# sensormain_Exodia_ver2.net
KiCad netlist of a schematic drawn in EAGLE
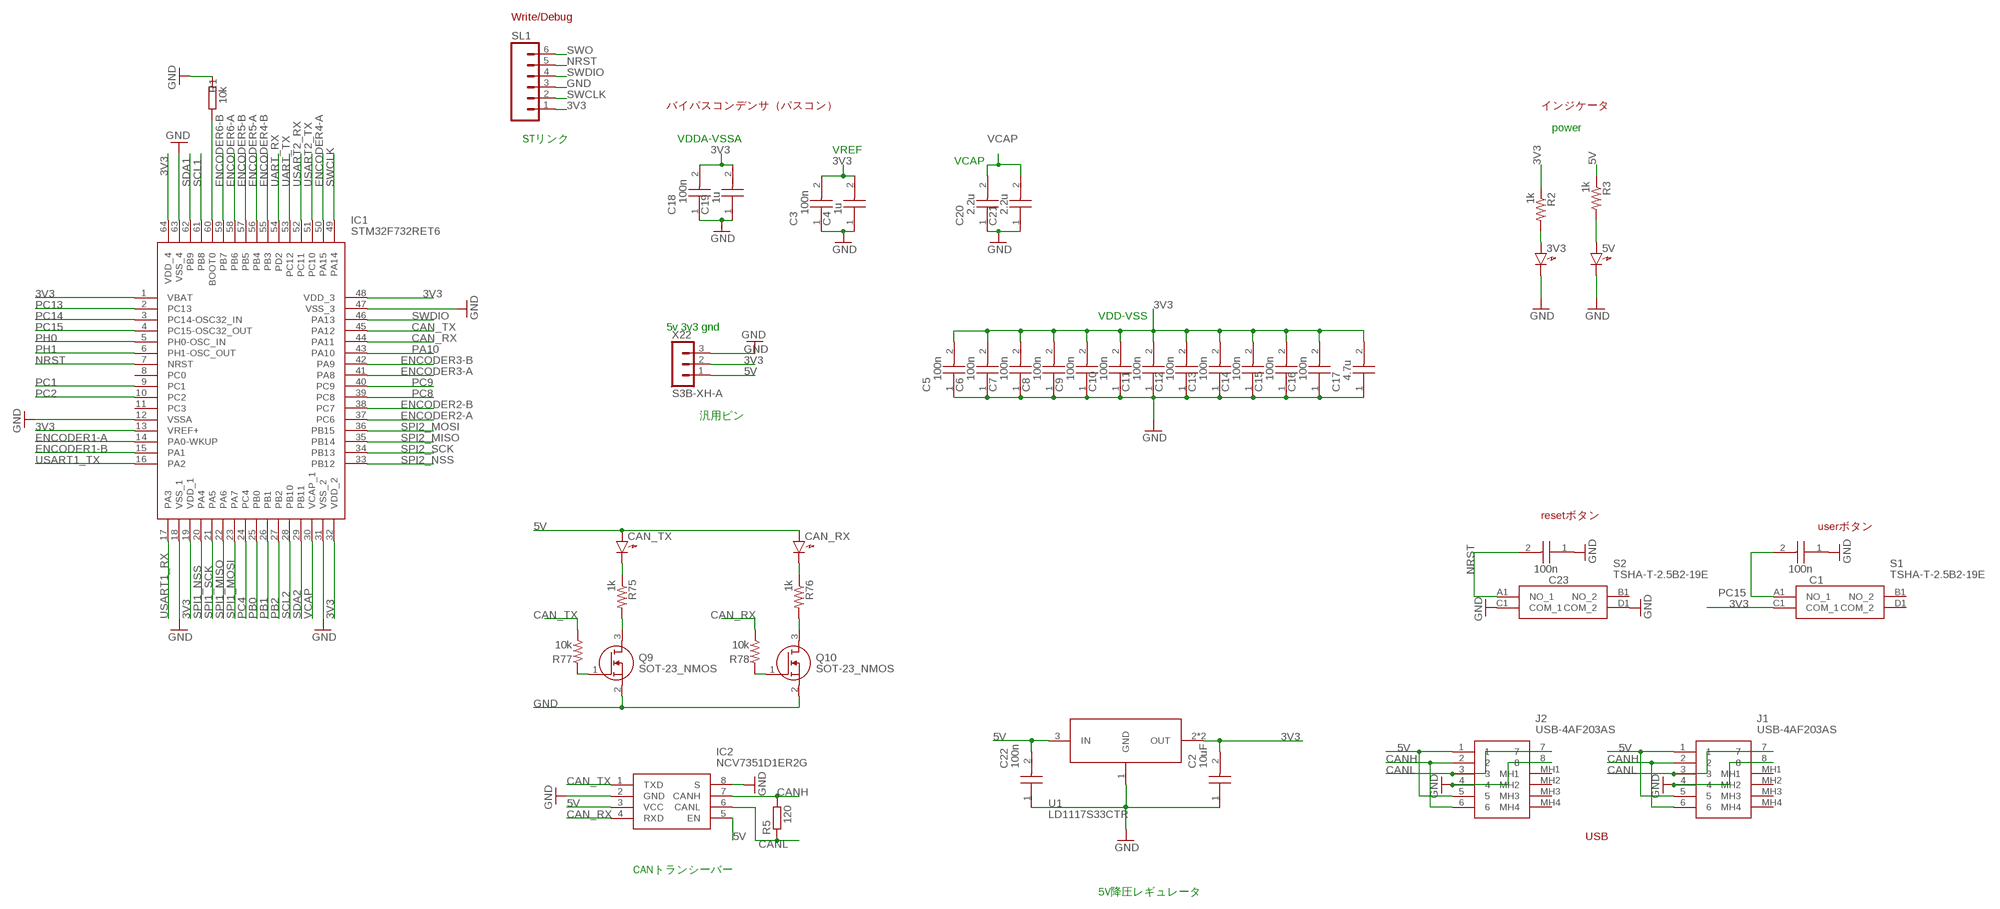
[diagram p0: schematic, sheet 1]
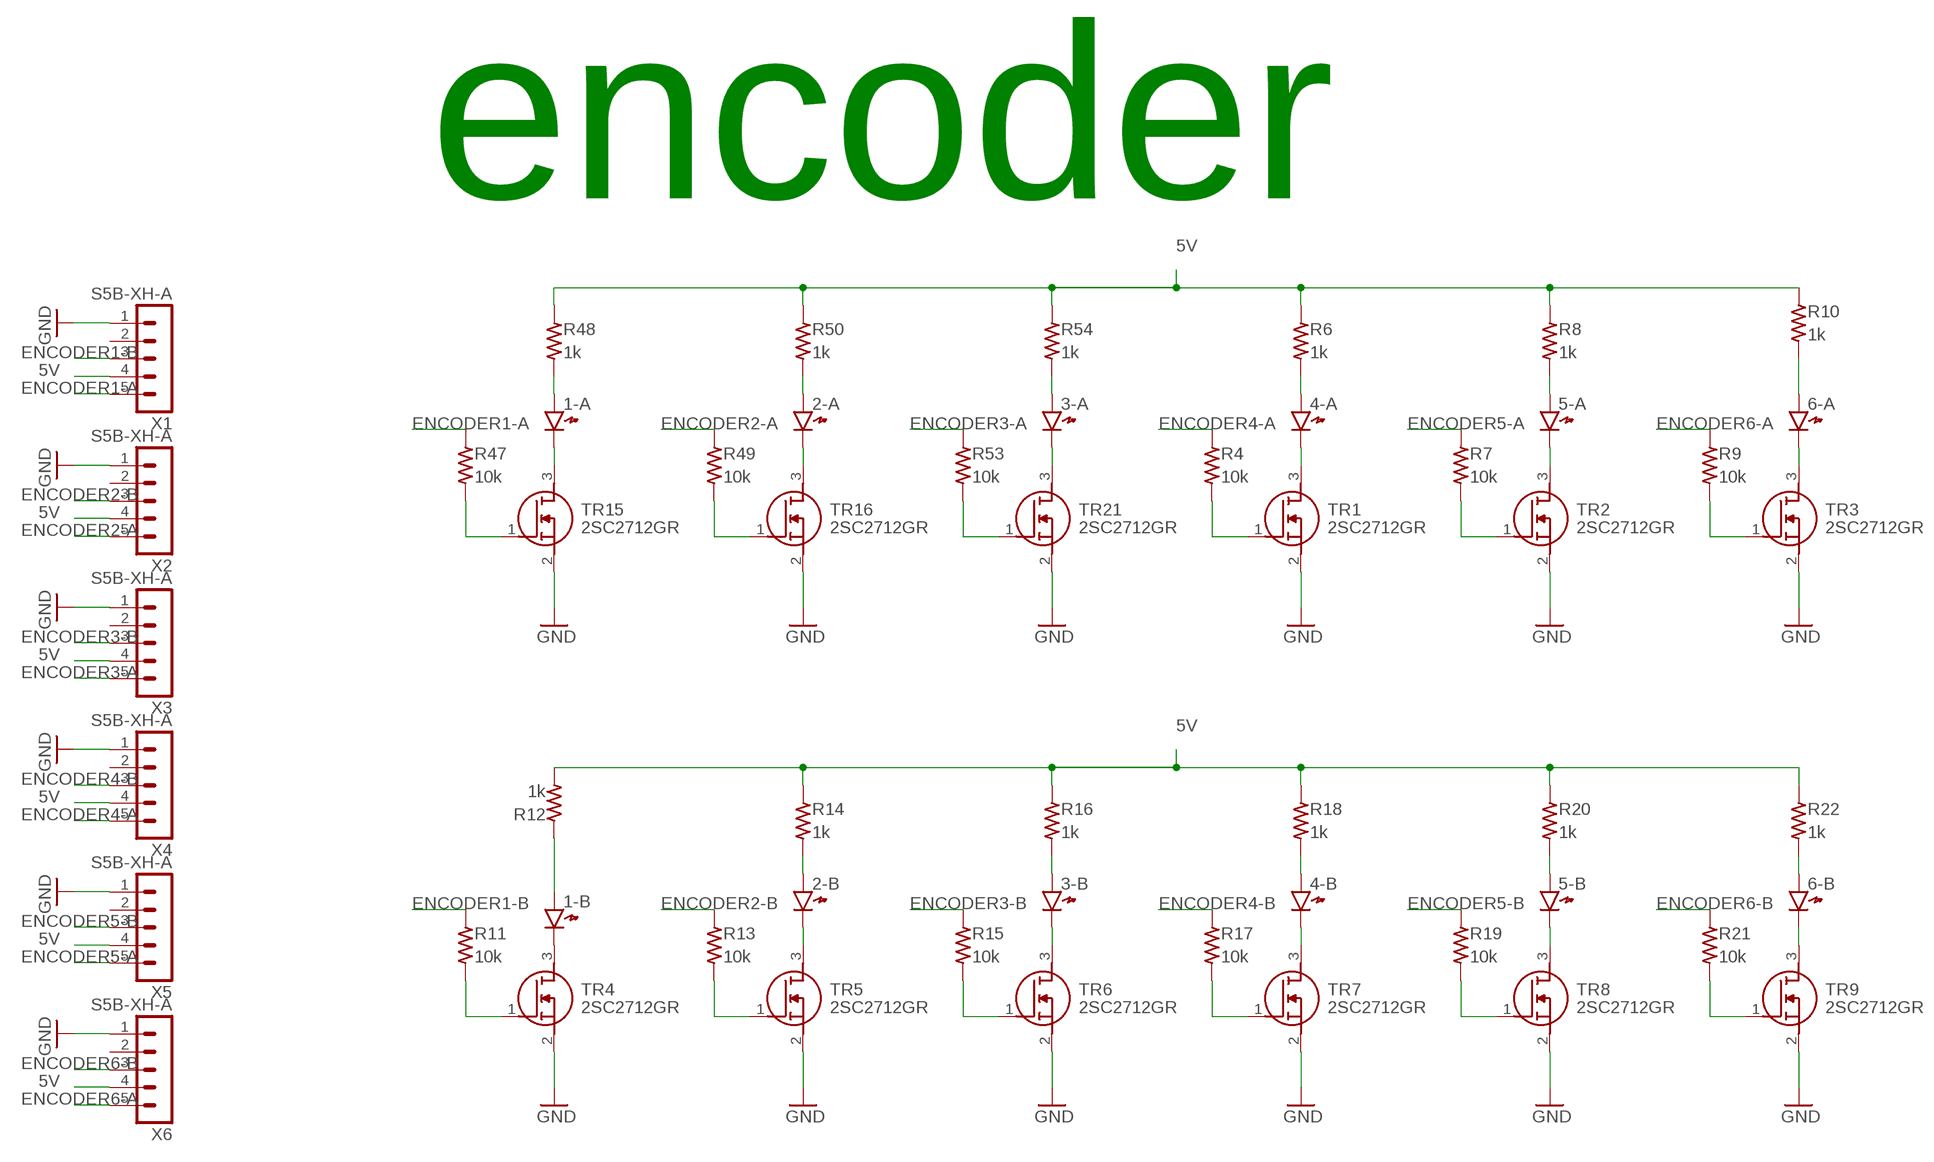
[diagram p1: schematic, sheet 2]
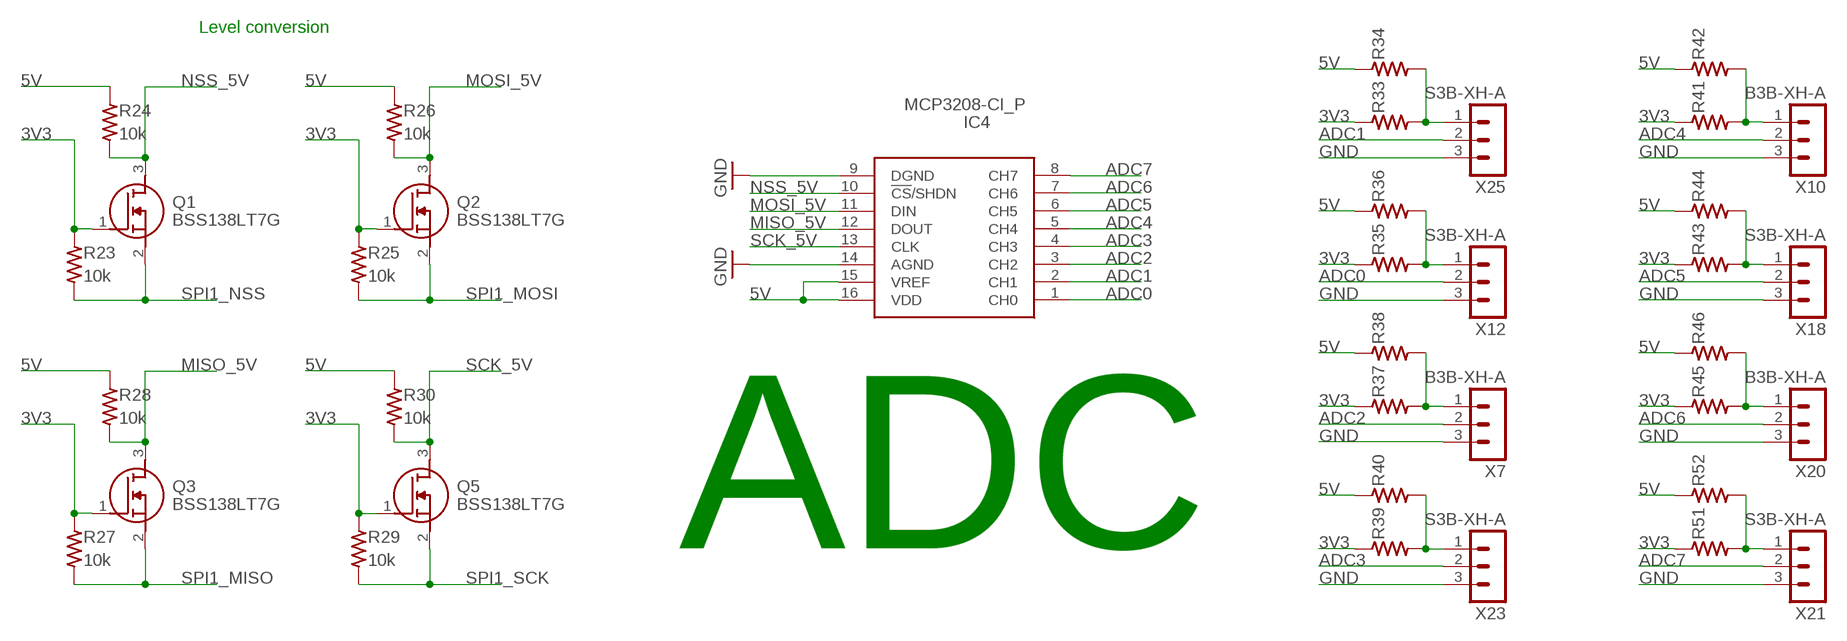
[diagram p2: schematic, sheet 3]
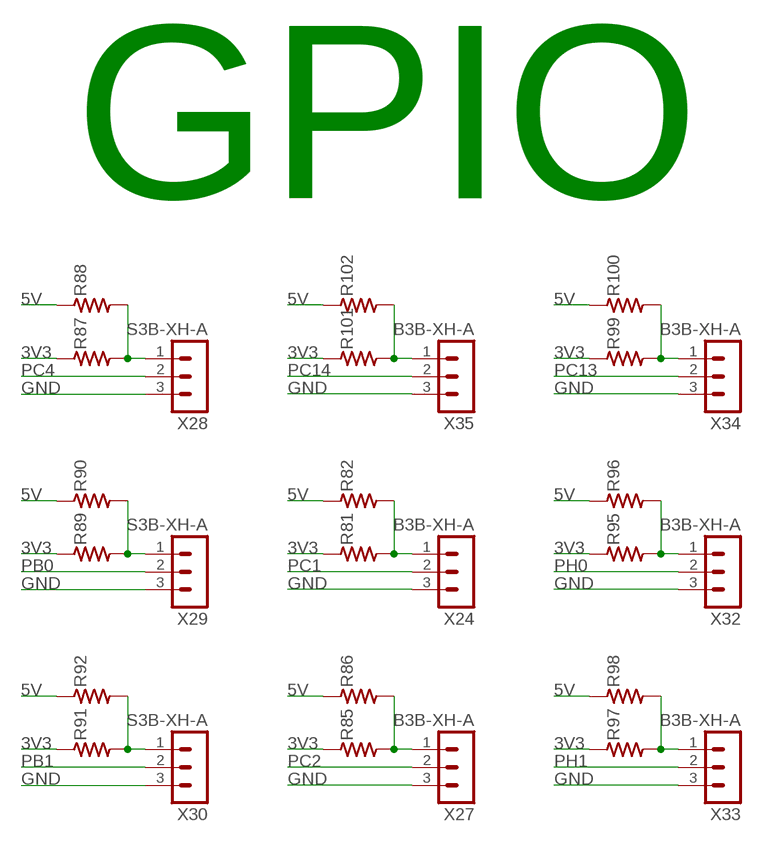
[diagram p3: schematic, sheet 4]
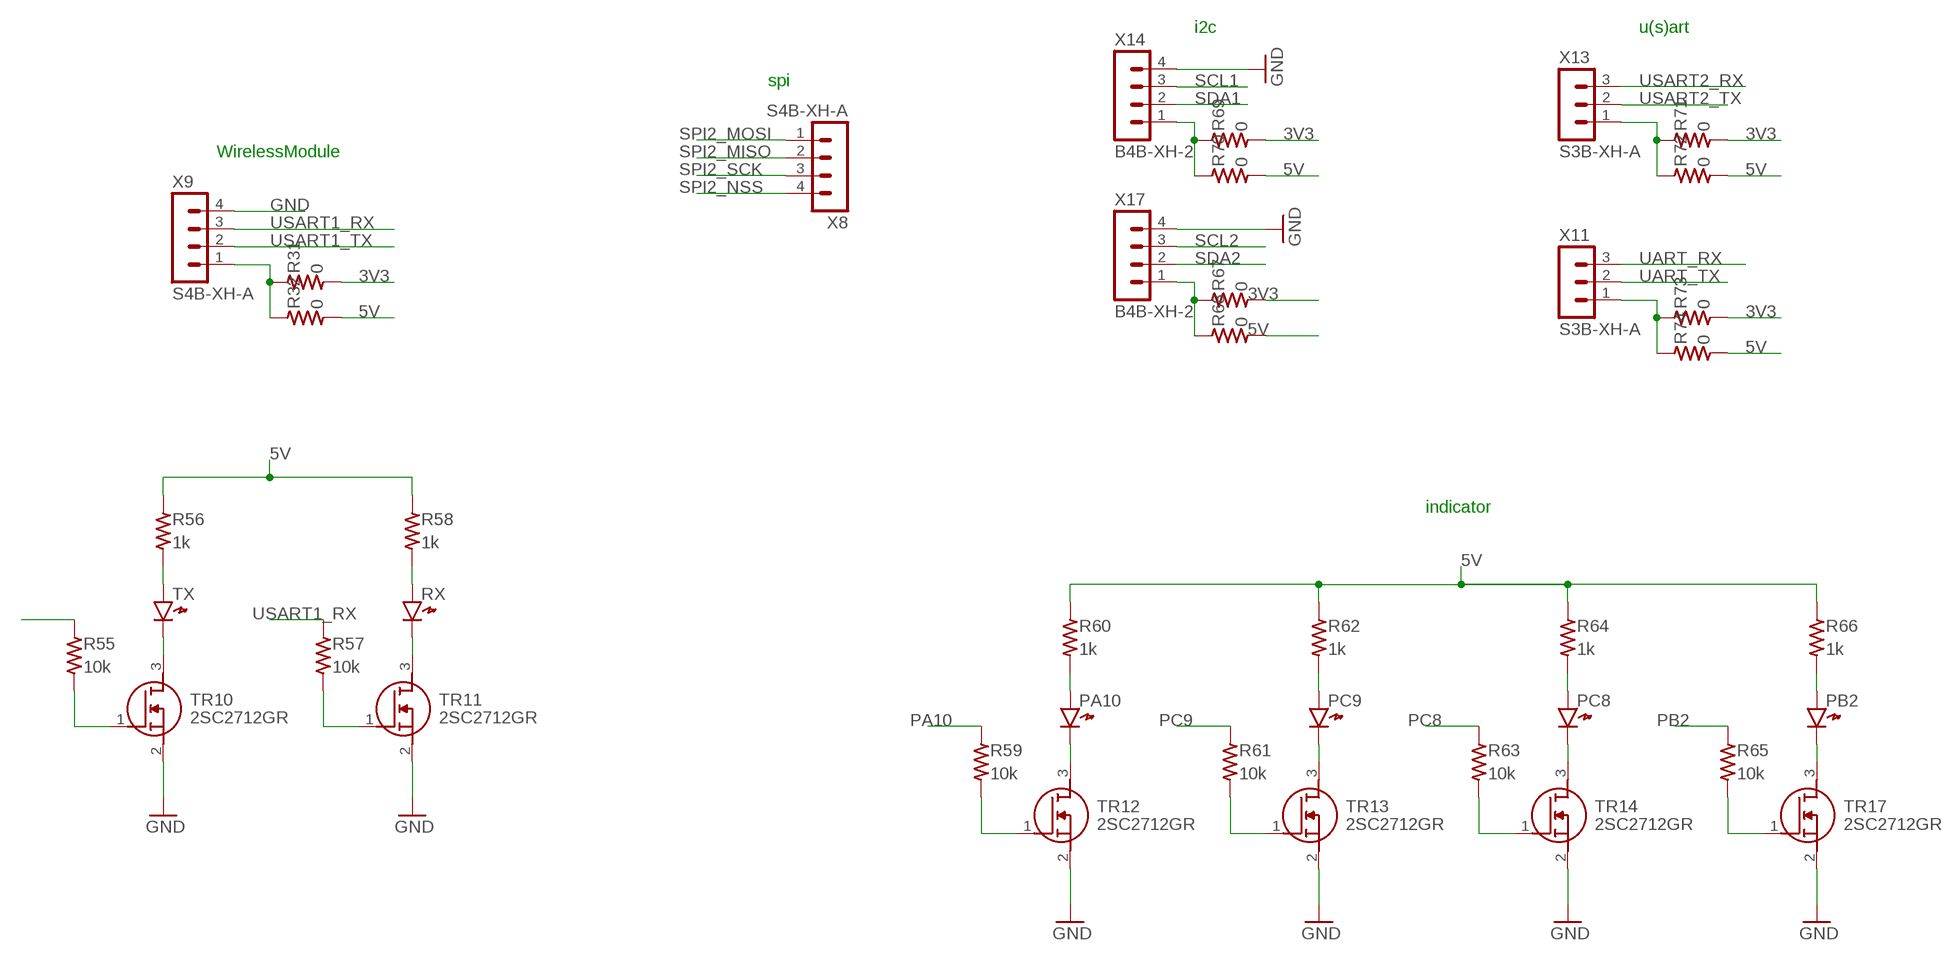
[diagram p4: schematic, sheet 5]

(export (version "E")
  (design (tool "Eeschema 10.0.6"))
  (components
    (comp (ref "IC4")
      (value "MCP3208-CI_P")
      (footprint "eagle-import:DIP781W56P254L1918H533Q16N")
      (fields
        (field (name "ARROW_PART_NUMBER") "MCP3208-CI/P")
        (field (name "MOUSER_PART_NUMBER") "579-MCP3208CIP")
      )
      (libsource (lib "eagle-import") (part "MCP3208-CI_P"))
    )
    (comp (ref "Q1")
      (value "BSS138LT7G")
      (footprint "eagle-import:SOT96P237X111-3N")
      (fields (field (name "MOUSER_PART_NUMBER") "863-BSS138LT7G"))
      (libsource (lib "eagle-import") (part "BSS138LT7G"))
    )
    (comp (ref "Q2")
      (value "BSS138LT7G")
      (footprint "eagle-import:SOT96P237X111-3N")
      (fields (field (name "MOUSER_PART_NUMBER") "863-BSS138LT7G"))
      (libsource (lib "eagle-import") (part "BSS138LT7G"))
    )
    (comp (ref "Q3")
      (value "BSS138LT7G")
      (footprint "eagle-import:SOT96P237X111-3N")
      (fields (field (name "MOUSER_PART_NUMBER") "863-BSS138LT7G"))
      (libsource (lib "eagle-import") (part "BSS138LT7G"))
    )
    (comp (ref "Q5")
      (value "BSS138LT7G")
      (footprint "eagle-import:SOT96P237X111-3N")
      (fields (field (name "MOUSER_PART_NUMBER") "863-BSS138LT7G"))
      (libsource (lib "eagle-import") (part "BSS138LT7G"))
    )
    (comp (ref "R23")
      (value "10k")
      (footprint "eagle-import:SMD1608")
      (libsource (lib "eagle-import") (part "RESISTOR-US1608"))
    )
    (comp (ref "R24")
      (value "10k")
      (footprint "eagle-import:SMD1608")
      (libsource (lib "eagle-import") (part "RESISTOR-US1608"))
    )
    (comp (ref "R25")
      (value "10k")
      (footprint "eagle-import:SMD1608")
      (libsource (lib "eagle-import") (part "RESISTOR-US1608"))
    )
    (comp (ref "R26")
      (value "10k")
      (footprint "eagle-import:SMD1608")
      (libsource (lib "eagle-import") (part "RESISTOR-US1608"))
    )
    (comp (ref "R27")
      (value "10k")
      (footprint "eagle-import:SMD1608")
      (libsource (lib "eagle-import") (part "RESISTOR-US1608"))
    )
    (comp (ref "R28")
      (value "10k")
      (footprint "eagle-import:SMD1608")
      (libsource (lib "eagle-import") (part "RESISTOR-US1608"))
    )
    (comp (ref "R29")
      (value "10k")
      (footprint "eagle-import:SMD1608")
      (libsource (lib "eagle-import") (part "RESISTOR-US1608"))
    )
    (comp (ref "R30")
      (value "10k")
      (footprint "eagle-import:SMD1608")
      (libsource (lib "eagle-import") (part "RESISTOR-US1608"))
    )
    (comp (ref "R33")
      (value "RESISTOR-US1608")
      (footprint "eagle-import:SMD1608")
      (libsource (lib "eagle-import") (part "RESISTOR-US1608"))
    )
    (comp (ref "R34")
      (value "RESISTOR-US1608")
      (footprint "eagle-import:SMD1608")
      (libsource (lib "eagle-import") (part "RESISTOR-US1608"))
    )
    (comp (ref "R35")
      (value "RESISTOR-US1608")
      (footprint "eagle-import:SMD1608")
      (libsource (lib "eagle-import") (part "RESISTOR-US1608"))
    )
    (comp (ref "R36")
      (value "RESISTOR-US1608")
      (footprint "eagle-import:SMD1608")
      (libsource (lib "eagle-import") (part "RESISTOR-US1608"))
    )
    (comp (ref "R37")
      (value "RESISTOR-US1608")
      (footprint "eagle-import:SMD1608")
      (libsource (lib "eagle-import") (part "RESISTOR-US1608"))
    )
    (comp (ref "R38")
      (value "RESISTOR-US1608")
      (footprint "eagle-import:SMD1608")
      (libsource (lib "eagle-import") (part "RESISTOR-US1608"))
    )
    (comp (ref "R39")
      (value "RESISTOR-US1608")
      (footprint "eagle-import:SMD1608")
      (libsource (lib "eagle-import") (part "RESISTOR-US1608"))
    )
    (comp (ref "R40")
      (value "RESISTOR-US1608")
      (footprint "eagle-import:SMD1608")
      (libsource (lib "eagle-import") (part "RESISTOR-US1608"))
    )
    (comp (ref "R41")
      (value "RESISTOR-US1608")
      (footprint "eagle-import:SMD1608")
      (libsource (lib "eagle-import") (part "RESISTOR-US1608"))
    )
    (comp (ref "R42")
      (value "RESISTOR-US1608")
      (footprint "eagle-import:SMD1608")
      (libsource (lib "eagle-import") (part "RESISTOR-US1608"))
    )
    (comp (ref "R43")
      (value "RESISTOR-US1608")
      (footprint "eagle-import:SMD1608")
      (libsource (lib "eagle-import") (part "RESISTOR-US1608"))
    )
    (comp (ref "R44")
      (value "RESISTOR-US1608")
      (footprint "eagle-import:SMD1608")
      (libsource (lib "eagle-import") (part "RESISTOR-US1608"))
    )
    (comp (ref "R45")
      (value "RESISTOR-US1608")
      (footprint "eagle-import:SMD1608")
      (libsource (lib "eagle-import") (part "RESISTOR-US1608"))
    )
    (comp (ref "R46")
      (value "RESISTOR-US1608")
      (footprint "eagle-import:SMD1608")
      (libsource (lib "eagle-import") (part "RESISTOR-US1608"))
    )
    (comp (ref "R51")
      (value "RESISTOR-US1608")
      (footprint "eagle-import:SMD1608")
      (libsource (lib "eagle-import") (part "RESISTOR-US1608"))
    )
    (comp (ref "R52")
      (value "RESISTOR-US1608")
      (footprint "eagle-import:SMD1608")
      (libsource (lib "eagle-import") (part "RESISTOR-US1608"))
    )
    (comp (ref "X7")
      (value "B3B-XH-A")
      (footprint "eagle-import:B3B-XH-A")
      (libsource (lib "eagle-import") (part "B3B-XH-A"))
    )
    (comp (ref "X10")
      (value "B3B-XH-A")
      (footprint "eagle-import:B3B-XH-A")
      (libsource (lib "eagle-import") (part "B3B-XH-A"))
    )
    (comp (ref "X12")
      (value "S3B-XH-A")
      (footprint "eagle-import:S3B-XH-A")
      (libsource (lib "eagle-import") (part "S3B-XH-A"))
    )
    (comp (ref "X18")
      (value "S3B-XH-A")
      (footprint "eagle-import:S3B-XH-A")
      (libsource (lib "eagle-import") (part "S3B-XH-A"))
    )
    (comp (ref "X20")
      (value "B3B-XH-A")
      (footprint "eagle-import:B3B-XH-A")
      (libsource (lib "eagle-import") (part "B3B-XH-A"))
    )
    (comp (ref "X21")
      (value "S3B-XH-A")
      (footprint "eagle-import:S3B-XH-A")
      (libsource (lib "eagle-import") (part "S3B-XH-A"))
    )
    (comp (ref "X23")
      (value "S3B-XH-A")
      (footprint "eagle-import:S3B-XH-A")
      (libsource (lib "eagle-import") (part "S3B-XH-A"))
    )
    (comp (ref "X25")
      (value "S3B-XH-A")
      (footprint "eagle-import:S3B-XH-A")
      (libsource (lib "eagle-import") (part "S3B-XH-A"))
    )
    (comp (ref "3V3")
      (value "LED1608")
      (footprint "eagle-import:LED1608")
      (libsource (lib "eagle-import") (part "LED1608"))
    )
    (comp (ref "5V")
      (value "LED1608")
      (footprint "eagle-import:LED1608")
      (libsource (lib "eagle-import") (part "LED1608"))
    )
    (comp (ref "C1")
      (value "100n")
      (footprint "eagle-import:CAPC1709X100N")
      (fields
        (field (name "MANUFACTURER_PART_NUMBER") "AMK107BBJ476MA-RE")
        (field (name "MOUSER_PART_NUMBER") "963-AMK107BBJ476MARE")
        (field (name "RS_PART_NUMBER") "1843762P")
      )
      (libsource (lib "eagle-import") (part "AMK107BBJ476MA-RE"))
    )
    (comp (ref "C2")
      (value "10uF")
      (footprint "eagle-import:CAPC1608X90N")
      (fields
        (field (name "MANUFACTURER_PART_NUMBER") "GRM188B31A106KE69D")
        (field (name "RS_PART_NUMBER") "8847157P")
      )
      (libsource (lib "eagle-import") (part "GRM188B31A106KE69D"))
    )
    (comp (ref "C3")
      (value "100n")
      (footprint "eagle-import:CAPC1709X100N")
      (fields
        (field (name "MANUFACTURER_PART_NUMBER") "AMK107BBJ476MA-RE")
        (field (name "MOUSER_PART_NUMBER") "963-AMK107BBJ476MARE")
        (field (name "RS_PART_NUMBER") "1843762P")
      )
      (libsource (lib "eagle-import") (part "AMK107BBJ476MA-RE"))
    )
    (comp (ref "C4")
      (value "1u")
      (footprint "eagle-import:CAPC1709X100N")
      (fields
        (field (name "MANUFACTURER_PART_NUMBER") "AMK107BBJ476MA-RE")
        (field (name "MOUSER_PART_NUMBER") "963-AMK107BBJ476MARE")
        (field (name "RS_PART_NUMBER") "1843762P")
      )
      (libsource (lib "eagle-import") (part "AMK107BBJ476MA-RE"))
    )
    (comp (ref "C5")
      (value "100n")
      (footprint "eagle-import:CAPC1709X100N")
      (fields
        (field (name "MANUFACTURER_PART_NUMBER") "AMK107BBJ476MA-RE")
        (field (name "MOUSER_PART_NUMBER") "963-AMK107BBJ476MARE")
        (field (name "RS_PART_NUMBER") "1843762P")
      )
      (libsource (lib "eagle-import") (part "AMK107BBJ476MA-RE"))
    )
    (comp (ref "C6")
      (value "100n")
      (footprint "eagle-import:CAPC1709X100N")
      (fields
        (field (name "MANUFACTURER_PART_NUMBER") "AMK107BBJ476MA-RE")
        (field (name "MOUSER_PART_NUMBER") "963-AMK107BBJ476MARE")
        (field (name "RS_PART_NUMBER") "1843762P")
      )
      (libsource (lib "eagle-import") (part "AMK107BBJ476MA-RE"))
    )
    (comp (ref "C7")
      (value "100n")
      (footprint "eagle-import:CAPC1709X100N")
      (fields
        (field (name "MANUFACTURER_PART_NUMBER") "AMK107BBJ476MA-RE")
        (field (name "MOUSER_PART_NUMBER") "963-AMK107BBJ476MARE")
        (field (name "RS_PART_NUMBER") "1843762P")
      )
      (libsource (lib "eagle-import") (part "AMK107BBJ476MA-RE"))
    )
    (comp (ref "C8")
      (value "100n")
      (footprint "eagle-import:CAPC1709X100N")
      (fields
        (field (name "MANUFACTURER_PART_NUMBER") "AMK107BBJ476MA-RE")
        (field (name "MOUSER_PART_NUMBER") "963-AMK107BBJ476MARE")
        (field (name "RS_PART_NUMBER") "1843762P")
      )
      (libsource (lib "eagle-import") (part "AMK107BBJ476MA-RE"))
    )
    (comp (ref "C9")
      (value "100n")
      (footprint "eagle-import:CAPC1709X100N")
      (fields
        (field (name "MANUFACTURER_PART_NUMBER") "AMK107BBJ476MA-RE")
        (field (name "MOUSER_PART_NUMBER") "963-AMK107BBJ476MARE")
        (field (name "RS_PART_NUMBER") "1843762P")
      )
      (libsource (lib "eagle-import") (part "AMK107BBJ476MA-RE"))
    )
    (comp (ref "C10")
      (value "100n")
      (footprint "eagle-import:CAPC1709X100N")
      (fields
        (field (name "MANUFACTURER_PART_NUMBER") "AMK107BBJ476MA-RE")
        (field (name "MOUSER_PART_NUMBER") "963-AMK107BBJ476MARE")
        (field (name "RS_PART_NUMBER") "1843762P")
      )
      (libsource (lib "eagle-import") (part "AMK107BBJ476MA-RE"))
    )
    (comp (ref "C11")
      (value "100n")
      (footprint "eagle-import:CAPC1709X100N")
      (fields
        (field (name "MANUFACTURER_PART_NUMBER") "AMK107BBJ476MA-RE")
        (field (name "MOUSER_PART_NUMBER") "963-AMK107BBJ476MARE")
        (field (name "RS_PART_NUMBER") "1843762P")
      )
      (libsource (lib "eagle-import") (part "AMK107BBJ476MA-RE"))
    )
    (comp (ref "C12")
      (value "100n")
      (footprint "eagle-import:CAPC1709X100N")
      (fields
        (field (name "MANUFACTURER_PART_NUMBER") "AMK107BBJ476MA-RE")
        (field (name "MOUSER_PART_NUMBER") "963-AMK107BBJ476MARE")
        (field (name "RS_PART_NUMBER") "1843762P")
      )
      (libsource (lib "eagle-import") (part "AMK107BBJ476MA-RE"))
    )
    (comp (ref "C13")
      (value "100n")
      (footprint "eagle-import:CAPC1709X100N")
      (fields
        (field (name "MANUFACTURER_PART_NUMBER") "AMK107BBJ476MA-RE")
        (field (name "MOUSER_PART_NUMBER") "963-AMK107BBJ476MARE")
        (field (name "RS_PART_NUMBER") "1843762P")
      )
      (libsource (lib "eagle-import") (part "AMK107BBJ476MA-RE"))
    )
    (comp (ref "C14")
      (value "100n")
      (footprint "eagle-import:CAPC1709X100N")
      (fields
        (field (name "MANUFACTURER_PART_NUMBER") "AMK107BBJ476MA-RE")
        (field (name "MOUSER_PART_NUMBER") "963-AMK107BBJ476MARE")
        (field (name "RS_PART_NUMBER") "1843762P")
      )
      (libsource (lib "eagle-import") (part "AMK107BBJ476MA-RE"))
    )
    (comp (ref "C15")
      (value "100n")
      (footprint "eagle-import:CAPC1709X100N")
      (fields
        (field (name "MANUFACTURER_PART_NUMBER") "AMK107BBJ476MA-RE")
        (field (name "MOUSER_PART_NUMBER") "963-AMK107BBJ476MARE")
        (field (name "RS_PART_NUMBER") "1843762P")
      )
      (libsource (lib "eagle-import") (part "AMK107BBJ476MA-RE"))
    )
    (comp (ref "C16")
      (value "100n")
      (footprint "eagle-import:CAPC1709X100N")
      (fields
        (field (name "MANUFACTURER_PART_NUMBER") "AMK107BBJ476MA-RE")
        (field (name "MOUSER_PART_NUMBER") "963-AMK107BBJ476MARE")
        (field (name "RS_PART_NUMBER") "1843762P")
      )
      (libsource (lib "eagle-import") (part "AMK107BBJ476MA-RE"))
    )
    (comp (ref "C17")
      (value "4.7u")
      (footprint "eagle-import:CAPC1709X100N")
      (fields
        (field (name "MANUFACTURER_PART_NUMBER") "AMK107BBJ476MA-RE")
        (field (name "MOUSER_PART_NUMBER") "963-AMK107BBJ476MARE")
        (field (name "RS_PART_NUMBER") "1843762P")
      )
      (libsource (lib "eagle-import") (part "AMK107BBJ476MA-RE"))
    )
    (comp (ref "C18")
      (value "100n")
      (footprint "eagle-import:CAPC1709X100N")
      (fields
        (field (name "MANUFACTURER_PART_NUMBER") "AMK107BBJ476MA-RE")
        (field (name "MOUSER_PART_NUMBER") "963-AMK107BBJ476MARE")
        (field (name "RS_PART_NUMBER") "1843762P")
      )
      (libsource (lib "eagle-import") (part "AMK107BBJ476MA-RE"))
    )
    (comp (ref "C19")
      (value "1u")
      (footprint "eagle-import:CAPC1709X100N")
      (fields
        (field (name "MANUFACTURER_PART_NUMBER") "AMK107BBJ476MA-RE")
        (field (name "MOUSER_PART_NUMBER") "963-AMK107BBJ476MARE")
        (field (name "RS_PART_NUMBER") "1843762P")
      )
      (libsource (lib "eagle-import") (part "AMK107BBJ476MA-RE"))
    )
    (comp (ref "C20")
      (value "2.2u")
      (footprint "eagle-import:CAPC1709X100N")
      (fields
        (field (name "MANUFACTURER_PART_NUMBER") "AMK107BBJ476MA-RE")
        (field (name "MOUSER_PART_NUMBER") "963-AMK107BBJ476MARE")
        (field (name "RS_PART_NUMBER") "1843762P")
      )
      (libsource (lib "eagle-import") (part "AMK107BBJ476MA-RE"))
    )
    (comp (ref "C21")
      (value "2.2u")
      (footprint "eagle-import:CAPC1709X100N")
      (fields
        (field (name "MANUFACTURER_PART_NUMBER") "AMK107BBJ476MA-RE")
        (field (name "MOUSER_PART_NUMBER") "963-AMK107BBJ476MARE")
        (field (name "RS_PART_NUMBER") "1843762P")
      )
      (libsource (lib "eagle-import") (part "AMK107BBJ476MA-RE"))
    )
    (comp (ref "C22")
      (value "100n")
      (footprint "eagle-import:CAPC1608X90N")
      (fields
        (field (name "MANUFACTURER_PART_NUMBER") "GRM188B31A106KE69D")
        (field (name "RS_PART_NUMBER") "8847157P")
      )
      (libsource (lib "eagle-import") (part "GRM188B31A106KE69D"))
    )
    (comp (ref "C23")
      (value "100n")
      (footprint "eagle-import:CAPC1709X100N")
      (fields
        (field (name "MANUFACTURER_PART_NUMBER") "AMK107BBJ476MA-RE")
        (field (name "MOUSER_PART_NUMBER") "963-AMK107BBJ476MARE")
        (field (name "RS_PART_NUMBER") "1843762P")
      )
      (libsource (lib "eagle-import") (part "AMK107BBJ476MA-RE"))
    )
    (comp (ref "CAN_RX")
      (value "LED1608")
      (footprint "eagle-import:LED1608")
      (libsource (lib "eagle-import") (part "LED1608"))
    )
    (comp (ref "CAN_TX")
      (value "LED1608")
      (footprint "eagle-import:LED1608")
      (libsource (lib "eagle-import") (part "LED1608"))
    )
    (comp (ref "IC1")
      (value "STM32F732RET6")
      (footprint "eagle-import:QFP50P1200X1200X160-64N")
      (fields (field (name "MOUSER_PART_NUMBER") "511-STM32F732RET6"))
      (libsource (lib "eagle-import") (part "STM32F732RET6"))
    )
    (comp (ref "IC2")
      (value "NCV7351D1ER2G")
      (footprint "eagle-import:SOIC127P600X175-8N")
      (fields (field (name "MOUSER_PART_NUMBER") "863-NCV7351D1ER2G"))
      (libsource (lib "eagle-import") (part "NCV7351D1ER2G"))
    )
    (comp (ref "J1")
      (value "USB-4AF203AS")
      (footprint "eagle-import:USB4AF203AS")
      (libsource (lib "eagle-import") (part "USB-4AF203AS"))
    )
    (comp (ref "J2")
      (value "USB-4AF203AS")
      (footprint "eagle-import:USB4AF203AS")
      (libsource (lib "eagle-import") (part "USB-4AF203AS"))
    )
    (comp (ref "Q9")
      (value "SOT-23_NMOS")
      (footprint "eagle-import:SOT-23")
      (libsource (lib "eagle-import") (part "SOT-23_NMOS"))
    )
    (comp (ref "Q10")
      (value "SOT-23_NMOS")
      (footprint "eagle-import:SOT-23")
      (libsource (lib "eagle-import") (part "SOT-23_NMOS"))
    )
    (comp (ref "R1")
      (value "10k")
      (footprint "eagle-import:1608")
      (libsource (lib "eagle-import") (part "R1608"))
    )
    (comp (ref "R2")
      (value "1k")
      (footprint "eagle-import:R0603")
      (libsource (lib "eagle-import") (part "R-US_R0603"))
    )
    (comp (ref "R3")
      (value "1k")
      (footprint "eagle-import:R0603")
      (libsource (lib "eagle-import") (part "R-US_R0603"))
    )
    (comp (ref "R5")
      (value "120")
      (footprint "eagle-import:R0805")
      (libsource (lib "eagle-import") (part "R-EU_R0805"))
    )
    (comp (ref "R75")
      (value "1k")
      (footprint "eagle-import:R0603")
      (libsource (lib "eagle-import") (part "R-US_R0603"))
    )
    (comp (ref "R76")
      (value "1k")
      (footprint "eagle-import:R0603")
      (libsource (lib "eagle-import") (part "R-US_R0603"))
    )
    (comp (ref "R77")
      (value "10k")
      (footprint "eagle-import:SMD1608")
      (libsource (lib "eagle-import") (part "RESISTOR-US1608"))
    )
    (comp (ref "R78")
      (value "10k")
      (footprint "eagle-import:SMD1608")
      (libsource (lib "eagle-import") (part "RESISTOR-US1608"))
    )
    (comp (ref "S1")
      (value "TSHA-T-2.5B2-19E")
      (footprint "eagle-import:TSHAT25B219E")
      (libsource (lib "eagle-import") (part "TSHA-T-2.5B2-19E"))
    )
    (comp (ref "S2")
      (value "TSHA-T-2.5B2-19E")
      (footprint "eagle-import:TSHAT25B219E")
      (libsource (lib "eagle-import") (part "TSHA-T-2.5B2-19E"))
    )
    (comp (ref "SL1")
      (value "MA06")
      (footprint "eagle-import:06PA")
      (libsource (lib "eagle-import") (part "MA06"))
    )
    (comp (ref "U1")
      (value "LD1117S33CTR")
      (footprint "eagle-import:SOT223")
      (fields (field (name "MF") "STMicroelectronics"))
      (libsource (lib "eagle-import") (part "LD1117S33CTR"))
    )
    (comp (ref "X22")
      (value "S3B-XH-A")
      (footprint "eagle-import:S3B-XH-A")
      (libsource (lib "eagle-import") (part "con-JST_XH_S3B-XH-A"))
    )
    (comp (ref "R81")
      (value "RESISTOR-US1608")
      (footprint "eagle-import:SMD1608")
      (libsource (lib "eagle-import") (part "RESISTOR-US1608"))
    )
    (comp (ref "R82")
      (value "RESISTOR-US1608")
      (footprint "eagle-import:SMD1608")
      (libsource (lib "eagle-import") (part "RESISTOR-US1608"))
    )
    (comp (ref "R85")
      (value "RESISTOR-US1608")
      (footprint "eagle-import:SMD1608")
      (libsource (lib "eagle-import") (part "RESISTOR-US1608"))
    )
    (comp (ref "R86")
      (value "RESISTOR-US1608")
      (footprint "eagle-import:SMD1608")
      (libsource (lib "eagle-import") (part "RESISTOR-US1608"))
    )
    (comp (ref "R87")
      (value "RESISTOR-US1608")
      (footprint "eagle-import:SMD1608")
      (libsource (lib "eagle-import") (part "RESISTOR-US1608"))
    )
    (comp (ref "R88")
      (value "RESISTOR-US1608")
      (footprint "eagle-import:SMD1608")
      (libsource (lib "eagle-import") (part "RESISTOR-US1608"))
    )
    (comp (ref "R89")
      (value "RESISTOR-US1608")
      (footprint "eagle-import:SMD1608")
      (libsource (lib "eagle-import") (part "RESISTOR-US1608"))
    )
    (comp (ref "R90")
      (value "RESISTOR-US1608")
      (footprint "eagle-import:SMD1608")
      (libsource (lib "eagle-import") (part "RESISTOR-US1608"))
    )
    (comp (ref "R91")
      (value "RESISTOR-US1608")
      (footprint "eagle-import:SMD1608")
      (libsource (lib "eagle-import") (part "RESISTOR-US1608"))
    )
    (comp (ref "R92")
      (value "RESISTOR-US1608")
      (footprint "eagle-import:SMD1608")
      (libsource (lib "eagle-import") (part "RESISTOR-US1608"))
    )
    (comp (ref "R95")
      (value "RESISTOR-US1608")
      (footprint "eagle-import:SMD1608")
      (libsource (lib "eagle-import") (part "RESISTOR-US1608"))
    )
    (comp (ref "R96")
      (value "RESISTOR-US1608")
      (footprint "eagle-import:SMD1608")
      (libsource (lib "eagle-import") (part "RESISTOR-US1608"))
    )
    (comp (ref "R97")
      (value "RESISTOR-US1608")
      (footprint "eagle-import:SMD1608")
      (libsource (lib "eagle-import") (part "RESISTOR-US1608"))
    )
    (comp (ref "R98")
      (value "RESISTOR-US1608")
      (footprint "eagle-import:SMD1608")
      (libsource (lib "eagle-import") (part "RESISTOR-US1608"))
    )
    (comp (ref "R99")
      (value "RESISTOR-US1608")
      (footprint "eagle-import:SMD1608")
      (libsource (lib "eagle-import") (part "RESISTOR-US1608"))
    )
    (comp (ref "R100")
      (value "RESISTOR-US1608")
      (footprint "eagle-import:SMD1608")
      (libsource (lib "eagle-import") (part "RESISTOR-US1608"))
    )
    (comp (ref "R101")
      (value "RESISTOR-US1608")
      (footprint "eagle-import:SMD1608")
      (libsource (lib "eagle-import") (part "RESISTOR-US1608"))
    )
    (comp (ref "R102")
      (value "RESISTOR-US1608")
      (footprint "eagle-import:SMD1608")
      (libsource (lib "eagle-import") (part "RESISTOR-US1608"))
    )
    (comp (ref "X24")
      (value "B3B-XH-A")
      (footprint "eagle-import:B3B-XH-A")
      (libsource (lib "eagle-import") (part "B3B-XH-A"))
    )
    (comp (ref "X27")
      (value "B3B-XH-A")
      (footprint "eagle-import:B3B-XH-A")
      (libsource (lib "eagle-import") (part "B3B-XH-A"))
    )
    (comp (ref "X28")
      (value "S3B-XH-A")
      (footprint "eagle-import:S3B-XH-A")
      (libsource (lib "eagle-import") (part "S3B-XH-A"))
    )
    (comp (ref "X29")
      (value "S3B-XH-A")
      (footprint "eagle-import:S3B-XH-A")
      (libsource (lib "eagle-import") (part "S3B-XH-A"))
    )
    (comp (ref "X30")
      (value "S3B-XH-A")
      (footprint "eagle-import:S3B-XH-A")
      (libsource (lib "eagle-import") (part "S3B-XH-A"))
    )
    (comp (ref "X32")
      (value "B3B-XH-A")
      (footprint "eagle-import:B3B-XH-A")
      (libsource (lib "eagle-import") (part "B3B-XH-A"))
    )
    (comp (ref "X33")
      (value "B3B-XH-A")
      (footprint "eagle-import:B3B-XH-A")
      (libsource (lib "eagle-import") (part "B3B-XH-A"))
    )
    (comp (ref "X34")
      (value "B3B-XH-A")
      (footprint "eagle-import:B3B-XH-A")
      (libsource (lib "eagle-import") (part "B3B-XH-A"))
    )
    (comp (ref "X35")
      (value "B3B-XH-A")
      (footprint "eagle-import:B3B-XH-A")
      (libsource (lib "eagle-import") (part "B3B-XH-A"))
    )
    (comp (ref "1-A")
      (value "LED1608")
      (footprint "eagle-import:LED1608")
      (libsource (lib "eagle-import") (part "LED1608"))
    )
    (comp (ref "1-B")
      (value "LED1608")
      (footprint "eagle-import:LED1608")
      (libsource (lib "eagle-import") (part "LED1608"))
    )
    (comp (ref "2-A")
      (value "LED1608")
      (footprint "eagle-import:LED1608")
      (libsource (lib "eagle-import") (part "LED1608"))
    )
    (comp (ref "2-B")
      (value "LED1608")
      (footprint "eagle-import:LED1608")
      (libsource (lib "eagle-import") (part "LED1608"))
    )
    (comp (ref "3-A")
      (value "LED1608")
      (footprint "eagle-import:LED1608")
      (libsource (lib "eagle-import") (part "LED1608"))
    )
    (comp (ref "3-B")
      (value "LED1608")
      (footprint "eagle-import:LED1608")
      (libsource (lib "eagle-import") (part "LED1608"))
    )
    (comp (ref "4-A")
      (value "LED1608")
      (footprint "eagle-import:LED1608")
      (libsource (lib "eagle-import") (part "LED1608"))
    )
    (comp (ref "4-B")
      (value "LED1608")
      (footprint "eagle-import:LED1608")
      (libsource (lib "eagle-import") (part "LED1608"))
    )
    (comp (ref "5-A")
      (value "LED1608")
      (footprint "eagle-import:LED1608")
      (libsource (lib "eagle-import") (part "LED1608"))
    )
    (comp (ref "5-B")
      (value "LED1608")
      (footprint "eagle-import:LED1608")
      (libsource (lib "eagle-import") (part "LED1608"))
    )
    (comp (ref "6-A")
      (value "LED1608")
      (footprint "eagle-import:LED1608")
      (libsource (lib "eagle-import") (part "LED1608"))
    )
    (comp (ref "6-B")
      (value "LED1608")
      (footprint "eagle-import:LED1608")
      (libsource (lib "eagle-import") (part "LED1608"))
    )
    (comp (ref "R4")
      (value "10k")
      (footprint "eagle-import:SMD1608")
      (libsource (lib "eagle-import") (part "RESISTOR-US1608"))
    )
    (comp (ref "R6")
      (value "1k")
      (footprint "eagle-import:SMD1608")
      (libsource (lib "eagle-import") (part "RESISTOR-US1608"))
    )
    (comp (ref "R7")
      (value "10k")
      (footprint "eagle-import:SMD1608")
      (libsource (lib "eagle-import") (part "RESISTOR-US1608"))
    )
    (comp (ref "R8")
      (value "1k")
      (footprint "eagle-import:SMD1608")
      (libsource (lib "eagle-import") (part "RESISTOR-US1608"))
    )
    (comp (ref "R9")
      (value "10k")
      (footprint "eagle-import:SMD1608")
      (libsource (lib "eagle-import") (part "RESISTOR-US1608"))
    )
    (comp (ref "R10")
      (value "1k")
      (footprint "eagle-import:SMD1608")
      (libsource (lib "eagle-import") (part "RESISTOR-US1608"))
    )
    (comp (ref "R11")
      (value "10k")
      (footprint "eagle-import:SMD1608")
      (libsource (lib "eagle-import") (part "RESISTOR-US1608"))
    )
    (comp (ref "R12")
      (value "1k")
      (footprint "eagle-import:SMD1608")
      (libsource (lib "eagle-import") (part "RESISTOR-US1608"))
    )
    (comp (ref "R13")
      (value "10k")
      (footprint "eagle-import:SMD1608")
      (libsource (lib "eagle-import") (part "RESISTOR-US1608"))
    )
    (comp (ref "R14")
      (value "1k")
      (footprint "eagle-import:SMD1608")
      (libsource (lib "eagle-import") (part "RESISTOR-US1608"))
    )
    (comp (ref "R15")
      (value "10k")
      (footprint "eagle-import:SMD1608")
      (libsource (lib "eagle-import") (part "RESISTOR-US1608"))
    )
    (comp (ref "R16")
      (value "1k")
      (footprint "eagle-import:SMD1608")
      (libsource (lib "eagle-import") (part "RESISTOR-US1608"))
    )
    (comp (ref "R17")
      (value "10k")
      (footprint "eagle-import:SMD1608")
      (libsource (lib "eagle-import") (part "RESISTOR-US1608"))
    )
    (comp (ref "R18")
      (value "1k")
      (footprint "eagle-import:SMD1608")
      (libsource (lib "eagle-import") (part "RESISTOR-US1608"))
    )
    (comp (ref "R19")
      (value "10k")
      (footprint "eagle-import:SMD1608")
      (libsource (lib "eagle-import") (part "RESISTOR-US1608"))
    )
    (comp (ref "R20")
      (value "1k")
      (footprint "eagle-import:SMD1608")
      (libsource (lib "eagle-import") (part "RESISTOR-US1608"))
    )
    (comp (ref "R21")
      (value "10k")
      (footprint "eagle-import:SMD1608")
      (libsource (lib "eagle-import") (part "RESISTOR-US1608"))
    )
    (comp (ref "R22")
      (value "1k")
      (footprint "eagle-import:SMD1608")
      (libsource (lib "eagle-import") (part "RESISTOR-US1608"))
    )
    (comp (ref "R47")
      (value "10k")
      (footprint "eagle-import:SMD1608")
      (libsource (lib "eagle-import") (part "RESISTOR-US1608"))
    )
    (comp (ref "R48")
      (value "1k")
      (footprint "eagle-import:SMD1608")
      (libsource (lib "eagle-import") (part "RESISTOR-US1608"))
    )
    (comp (ref "R49")
      (value "10k")
      (footprint "eagle-import:SMD1608")
      (libsource (lib "eagle-import") (part "RESISTOR-US1608"))
    )
    (comp (ref "R50")
      (value "1k")
      (footprint "eagle-import:SMD1608")
      (libsource (lib "eagle-import") (part "RESISTOR-US1608"))
    )
    (comp (ref "R53")
      (value "10k")
      (footprint "eagle-import:SMD1608")
      (libsource (lib "eagle-import") (part "RESISTOR-US1608"))
    )
    (comp (ref "R54")
      (value "1k")
      (footprint "eagle-import:SMD1608")
      (libsource (lib "eagle-import") (part "RESISTOR-US1608"))
    )
    (comp (ref "TR1")
      (value "2SC2712GR")
      (footprint "eagle-import:SOT-23")
      (libsource (lib "eagle-import") (part "SOT-23_NMOS"))
    )
    (comp (ref "TR2")
      (value "2SC2712GR")
      (footprint "eagle-import:SOT-23")
      (libsource (lib "eagle-import") (part "SOT-23_NMOS"))
    )
    (comp (ref "TR3")
      (value "2SC2712GR")
      (footprint "eagle-import:SOT-23")
      (libsource (lib "eagle-import") (part "SOT-23_NMOS"))
    )
    (comp (ref "TR4")
      (value "2SC2712GR")
      (footprint "eagle-import:SOT-23")
      (libsource (lib "eagle-import") (part "SOT-23_NMOS"))
    )
    (comp (ref "TR5")
      (value "2SC2712GR")
      (footprint "eagle-import:SOT-23")
      (libsource (lib "eagle-import") (part "SOT-23_NMOS"))
    )
    (comp (ref "TR6")
      (value "2SC2712GR")
      (footprint "eagle-import:SOT-23")
      (libsource (lib "eagle-import") (part "SOT-23_NMOS"))
    )
    (comp (ref "TR7")
      (value "2SC2712GR")
      (footprint "eagle-import:SOT-23")
      (libsource (lib "eagle-import") (part "SOT-23_NMOS"))
    )
    (comp (ref "TR8")
      (value "2SC2712GR")
      (footprint "eagle-import:SOT-23")
      (libsource (lib "eagle-import") (part "SOT-23_NMOS"))
    )
    (comp (ref "TR9")
      (value "2SC2712GR")
      (footprint "eagle-import:SOT-23")
      (libsource (lib "eagle-import") (part "SOT-23_NMOS"))
    )
    (comp (ref "TR15")
      (value "2SC2712GR")
      (footprint "eagle-import:SOT-23")
      (libsource (lib "eagle-import") (part "SOT-23_NMOS"))
    )
    (comp (ref "TR16")
      (value "2SC2712GR")
      (footprint "eagle-import:SOT-23")
      (libsource (lib "eagle-import") (part "SOT-23_NMOS"))
    )
    (comp (ref "TR21")
      (value "2SC2712GR")
      (footprint "eagle-import:SOT-23")
      (libsource (lib "eagle-import") (part "SOT-23_NMOS"))
    )
    (comp (ref "X1")
      (value "S5B-XH-A")
      (footprint "eagle-import:S5B-XH-A")
      (libsource (lib "eagle-import") (part "S5B-XH-A"))
    )
    (comp (ref "X2")
      (value "S5B-XH-A")
      (footprint "eagle-import:S5B-XH-A")
      (libsource (lib "eagle-import") (part "S5B-XH-A"))
    )
    (comp (ref "X3")
      (value "S5B-XH-A")
      (footprint "eagle-import:S5B-XH-A")
      (libsource (lib "eagle-import") (part "S5B-XH-A"))
    )
    (comp (ref "X4")
      (value "S5B-XH-A")
      (footprint "eagle-import:S5B-XH-A")
      (libsource (lib "eagle-import") (part "S5B-XH-A"))
    )
    (comp (ref "X5")
      (value "S5B-XH-A")
      (footprint "eagle-import:S5B-XH-A")
      (libsource (lib "eagle-import") (part "S5B-XH-A"))
    )
    (comp (ref "X6")
      (value "S5B-XH-A")
      (footprint "eagle-import:S5B-XH-A")
      (libsource (lib "eagle-import") (part "S5B-XH-A"))
    )
    (comp (ref "PA10")
      (value "LED1608")
      (footprint "eagle-import:LED1608")
      (libsource (lib "eagle-import") (part "LED1608"))
    )
    (comp (ref "PB2")
      (value "LED1608")
      (footprint "eagle-import:LED1608")
      (libsource (lib "eagle-import") (part "LED1608"))
    )
    (comp (ref "PC8")
      (value "LED1608")
      (footprint "eagle-import:LED1608")
      (libsource (lib "eagle-import") (part "LED1608"))
    )
    (comp (ref "PC9")
      (value "LED1608")
      (footprint "eagle-import:LED1608")
      (libsource (lib "eagle-import") (part "LED1608"))
    )
    (comp (ref "R31")
      (value "0")
      (footprint "eagle-import:SMD1608")
      (libsource (lib "eagle-import") (part "RESISTOR-US1608"))
    )
    (comp (ref "R32")
      (value "0")
      (footprint "eagle-import:SMD1608")
      (libsource (lib "eagle-import") (part "RESISTOR-US1608"))
    )
    (comp (ref "R55")
      (value "10k")
      (footprint "eagle-import:SMD1608")
      (libsource (lib "eagle-import") (part "RESISTOR-US1608"))
    )
    (comp (ref "R56")
      (value "1k")
      (footprint "eagle-import:SMD1608")
      (libsource (lib "eagle-import") (part "RESISTOR-US1608"))
    )
    (comp (ref "R57")
      (value "10k")
      (footprint "eagle-import:SMD1608")
      (libsource (lib "eagle-import") (part "RESISTOR-US1608"))
    )
    (comp (ref "R58")
      (value "1k")
      (footprint "eagle-import:SMD1608")
      (libsource (lib "eagle-import") (part "RESISTOR-US1608"))
    )
    (comp (ref "R59")
      (value "10k")
      (footprint "eagle-import:SMD1608")
      (libsource (lib "eagle-import") (part "RESISTOR-US1608"))
    )
    (comp (ref "R60")
      (value "1k")
      (footprint "eagle-import:SMD1608")
      (libsource (lib "eagle-import") (part "RESISTOR-US1608"))
    )
    (comp (ref "R61")
      (value "10k")
      (footprint "eagle-import:SMD1608")
      (libsource (lib "eagle-import") (part "RESISTOR-US1608"))
    )
    (comp (ref "R62")
      (value "1k")
      (footprint "eagle-import:SMD1608")
      (libsource (lib "eagle-import") (part "RESISTOR-US1608"))
    )
    (comp (ref "R63")
      (value "10k")
      (footprint "eagle-import:SMD1608")
      (libsource (lib "eagle-import") (part "RESISTOR-US1608"))
    )
    (comp (ref "R64")
      (value "1k")
      (footprint "eagle-import:SMD1608")
      (libsource (lib "eagle-import") (part "RESISTOR-US1608"))
    )
    (comp (ref "R65")
      (value "10k")
      (footprint "eagle-import:SMD1608")
      (libsource (lib "eagle-import") (part "RESISTOR-US1608"))
    )
    (comp (ref "R66")
      (value "1k")
      (footprint "eagle-import:SMD1608")
      (libsource (lib "eagle-import") (part "RESISTOR-US1608"))
    )
    (comp (ref "R67")
      (value "0")
      (footprint "eagle-import:SMD1608")
      (libsource (lib "eagle-import") (part "RESISTOR-US1608"))
    )
    (comp (ref "R68")
      (value "0")
      (footprint "eagle-import:SMD1608")
      (libsource (lib "eagle-import") (part "RESISTOR-US1608"))
    )
    (comp (ref "R69")
      (value "0")
      (footprint "eagle-import:SMD1608")
      (libsource (lib "eagle-import") (part "RESISTOR-US1608"))
    )
    (comp (ref "R70")
      (value "0")
      (footprint "eagle-import:SMD1608")
      (libsource (lib "eagle-import") (part "RESISTOR-US1608"))
    )
    (comp (ref "R71")
      (value "0")
      (footprint "eagle-import:SMD1608")
      (libsource (lib "eagle-import") (part "RESISTOR-US1608"))
    )
    (comp (ref "R72")
      (value "0")
      (footprint "eagle-import:SMD1608")
      (libsource (lib "eagle-import") (part "RESISTOR-US1608"))
    )
    (comp (ref "R73")
      (value "0")
      (footprint "eagle-import:SMD1608")
      (libsource (lib "eagle-import") (part "RESISTOR-US1608"))
    )
    (comp (ref "R74")
      (value "0")
      (footprint "eagle-import:SMD1608")
      (libsource (lib "eagle-import") (part "RESISTOR-US1608"))
    )
    (comp (ref "RX")
      (value "LED1608")
      (footprint "eagle-import:LED1608")
      (libsource (lib "eagle-import") (part "LED1608"))
    )
    (comp (ref "TR10")
      (value "2SC2712GR")
      (footprint "eagle-import:SOT-23")
      (libsource (lib "eagle-import") (part "SOT-23_NMOS"))
    )
    (comp (ref "TR11")
      (value "2SC2712GR")
      (footprint "eagle-import:SOT-23")
      (libsource (lib "eagle-import") (part "SOT-23_NMOS"))
    )
    (comp (ref "TR12")
      (value "2SC2712GR")
      (footprint "eagle-import:SOT-23")
      (libsource (lib "eagle-import") (part "SOT-23_NMOS"))
    )
    (comp (ref "TR13")
      (value "2SC2712GR")
      (footprint "eagle-import:SOT-23")
      (libsource (lib "eagle-import") (part "SOT-23_NMOS"))
    )
    (comp (ref "TR14")
      (value "2SC2712GR")
      (footprint "eagle-import:SOT-23")
      (libsource (lib "eagle-import") (part "SOT-23_NMOS"))
    )
    (comp (ref "TR17")
      (value "2SC2712GR")
      (footprint "eagle-import:SOT-23")
      (libsource (lib "eagle-import") (part "SOT-23_NMOS"))
    )
    (comp (ref "TX")
      (value "LED1608")
      (footprint "eagle-import:LED1608")
      (libsource (lib "eagle-import") (part "LED1608"))
    )
    (comp (ref "X8")
      (value "S4B-XH-A")
      (footprint "eagle-import:S4B-XH-A")
      (libsource (lib "eagle-import") (part "S4B-XH-A"))
    )
    (comp (ref "X9")
      (value "S4B-XH-A")
      (footprint "eagle-import:S4B-XH-A")
      (libsource (lib "eagle-import") (part "S4B-XH-A"))
    )
    (comp (ref "X11")
      (value "S3B-XH-A")
      (footprint "eagle-import:S3B-XH-A")
      (libsource (lib "eagle-import") (part "S3B-XH-A"))
    )
    (comp (ref "X13")
      (value "S3B-XH-A")
      (footprint "eagle-import:S3B-XH-A")
      (libsource (lib "eagle-import") (part "S3B-XH-A"))
    )
    (comp (ref "X14")
      (value "B4B-XH-2")
      (footprint "eagle-import:B4B-XH-A")
      (libsource (lib "eagle-import") (part "B4B-XH-2"))
    )
    (comp (ref "X17")
      (value "B4B-XH-2")
      (footprint "eagle-import:B4B-XH-A")
      (libsource (lib "eagle-import") (part "B4B-XH-2"))
    )
  )
  (nets
    (net (code "1") (name "3V3") (class "Default")
      (node (ref "C10") (pin "2") (pinfunction "2_2") (pintype "bidirectional"))
      (node (ref "C11") (pin "2") (pinfunction "2_2") (pintype "bidirectional"))
      (node (ref "C12") (pin "2") (pinfunction "2_2") (pintype "bidirectional"))
      (node (ref "C13") (pin "2") (pinfunction "2_2") (pintype "bidirectional"))
      (node (ref "C14") (pin "2") (pinfunction "2_2") (pintype "bidirectional"))
      (node (ref "C15") (pin "2") (pinfunction "2_2") (pintype "bidirectional"))
      (node (ref "C16") (pin "2") (pinfunction "2_2") (pintype "bidirectional"))
      (node (ref "C17") (pin "2") (pinfunction "2_2") (pintype "bidirectional"))
      (node (ref "C18") (pin "2") (pinfunction "2_2") (pintype "bidirectional"))
      (node (ref "C19") (pin "2") (pinfunction "2_2") (pintype "bidirectional"))
      (node (ref "C2") (pin "2") (pinfunction "2_2") (pintype "bidirectional"))
      (node (ref "C3") (pin "2") (pinfunction "2_2") (pintype "bidirectional"))
      (node (ref "C4") (pin "2") (pinfunction "2_2") (pintype "bidirectional"))
      (node (ref "C5") (pin "2") (pinfunction "2_2") (pintype "bidirectional"))
      (node (ref "C6") (pin "2") (pinfunction "2_2") (pintype "bidirectional"))
      (node (ref "C7") (pin "2") (pinfunction "2_2") (pintype "bidirectional"))
      (node (ref "C8") (pin "2") (pinfunction "2_2") (pintype "bidirectional"))
      (node (ref "C9") (pin "2") (pinfunction "2_2") (pintype "bidirectional"))
      (node (ref "IC1") (pin "1") (pinfunction "VBAT_1") (pintype "power_in"))
      (node (ref "IC1") (pin "13") (pinfunction "VREF+_13") (pintype "power_in"))
      (node (ref "IC1") (pin "19") (pinfunction "VDD_1_19") (pintype "power_in"))
      (node (ref "IC1") (pin "32") (pinfunction "VDD_2_32") (pintype "power_in"))
      (node (ref "IC1") (pin "48") (pinfunction "VDD_3_48") (pintype "power_in"))
      (node (ref "IC1") (pin "64") (pinfunction "VDD_4_64") (pintype "power_in"))
      (node (ref "Q1") (pin "1") (pinfunction "G_1") (pintype "bidirectional"))
      (node (ref "Q2") (pin "1") (pinfunction "G_1") (pintype "bidirectional"))
      (node (ref "Q3") (pin "1") (pinfunction "G_1") (pintype "bidirectional"))
      (node (ref "Q5") (pin "1") (pinfunction "G_1") (pintype "bidirectional"))
      (node (ref "R101") (pin "1") (pinfunction "1_1") (pintype "passive"))
      (node (ref "R2") (pin "1") (pinfunction "1_1") (pintype "passive"))
      (node (ref "R23") (pin "1") (pinfunction "1_1") (pintype "passive"))
      (node (ref "R25") (pin "1") (pinfunction "1_1") (pintype "passive"))
      (node (ref "R27") (pin "1") (pinfunction "1_1") (pintype "passive"))
      (node (ref "R29") (pin "1") (pinfunction "1_1") (pintype "passive"))
      (node (ref "R31") (pin "2") (pinfunction "2_2") (pintype "passive"))
      (node (ref "R33") (pin "1") (pinfunction "1_1") (pintype "passive"))
      (node (ref "R35") (pin "1") (pinfunction "1_1") (pintype "passive"))
      (node (ref "R37") (pin "1") (pinfunction "1_1") (pintype "passive"))
      (node (ref "R39") (pin "1") (pinfunction "1_1") (pintype "passive"))
      (node (ref "R41") (pin "1") (pinfunction "1_1") (pintype "passive"))
      (node (ref "R43") (pin "1") (pinfunction "1_1") (pintype "passive"))
      (node (ref "R45") (pin "1") (pinfunction "1_1") (pintype "passive"))
      (node (ref "R51") (pin "1") (pinfunction "1_1") (pintype "passive"))
      (node (ref "R67") (pin "2") (pinfunction "2_2") (pintype "passive"))
      (node (ref "R69") (pin "2") (pinfunction "2_2") (pintype "passive"))
      (node (ref "R71") (pin "2") (pinfunction "2_2") (pintype "passive"))
      (node (ref "R73") (pin "2") (pinfunction "2_2") (pintype "passive"))
      (node (ref "R81") (pin "1") (pinfunction "1_1") (pintype "passive"))
      (node (ref "R85") (pin "1") (pinfunction "1_1") (pintype "passive"))
      (node (ref "R87") (pin "1") (pinfunction "1_1") (pintype "passive"))
      (node (ref "R89") (pin "1") (pinfunction "1_1") (pintype "passive"))
      (node (ref "R91") (pin "1") (pinfunction "1_1") (pintype "passive"))
      (node (ref "R95") (pin "1") (pinfunction "1_1") (pintype "passive"))
      (node (ref "R97") (pin "1") (pinfunction "1_1") (pintype "passive"))
      (node (ref "R99") (pin "1") (pinfunction "1_1") (pintype "passive"))
      (node (ref "S1") (pin "C1") (pinfunction "COM_1_C1") (pintype "bidirectional"))
      (node (ref "SL1") (pin "1") (pinfunction "1_1") (pintype "passive"))
      (node (ref "U1") (pin "2") (pinfunction "OUT_2") (pintype "output"))
      (node (ref "U1") (pin "4") (pinfunction "OUT_4") (pintype "output"))
      (node (ref "X22") (pin "2") (pinfunction "2_2") (pintype "passive"))
    )
    (net (code "2") (name "5V") (class "Default")
      (node (ref "C22") (pin "2") (pinfunction "2_2") (pintype "bidirectional"))
      (node (ref "CAN_RX") (pin "A") (pinfunction "A_A") (pintype "passive"))
      (node (ref "CAN_TX") (pin "A") (pinfunction "A_A") (pintype "passive"))
      (node (ref "IC2") (pin "3") (pinfunction "VCC_3") (pintype "bidirectional"))
      (node (ref "IC2") (pin "5") (pinfunction "EN_5") (pintype "bidirectional"))
      (node (ref "IC4") (pin "15") (pinfunction "VREF_15") (pintype "bidirectional"))
      (node (ref "IC4") (pin "16") (pinfunction "VDD_16") (pintype "bidirectional"))
      (node (ref "J1") (pin "1") (pinfunction "1_1") (pintype "bidirectional"))
      (node (ref "J1") (pin "5") (pinfunction "5_5") (pintype "bidirectional"))
      (node (ref "J2") (pin "1") (pinfunction "1_1") (pintype "bidirectional"))
      (node (ref "J2") (pin "5") (pinfunction "5_5") (pintype "bidirectional"))
      (node (ref "R10") (pin "1") (pinfunction "1_1") (pintype "passive"))
      (node (ref "R100") (pin "1") (pinfunction "1_1") (pintype "passive"))
      (node (ref "R102") (pin "1") (pinfunction "1_1") (pintype "passive"))
      (node (ref "R12") (pin "2") (pinfunction "2_2") (pintype "passive"))
      (node (ref "R14") (pin "1") (pinfunction "1_1") (pintype "passive"))
      (node (ref "R16") (pin "1") (pinfunction "1_1") (pintype "passive"))
      (node (ref "R18") (pin "1") (pinfunction "1_1") (pintype "passive"))
      (node (ref "R20") (pin "1") (pinfunction "1_1") (pintype "passive"))
      (node (ref "R22") (pin "1") (pinfunction "1_1") (pintype "passive"))
      (node (ref "R24") (pin "1") (pinfunction "1_1") (pintype "passive"))
      (node (ref "R26") (pin "1") (pinfunction "1_1") (pintype "passive"))
      (node (ref "R28") (pin "1") (pinfunction "1_1") (pintype "passive"))
      (node (ref "R3") (pin "1") (pinfunction "1_1") (pintype "passive"))
      (node (ref "R30") (pin "1") (pinfunction "1_1") (pintype "passive"))
      (node (ref "R32") (pin "2") (pinfunction "2_2") (pintype "passive"))
      (node (ref "R34") (pin "1") (pinfunction "1_1") (pintype "passive"))
      (node (ref "R36") (pin "1") (pinfunction "1_1") (pintype "passive"))
      (node (ref "R38") (pin "1") (pinfunction "1_1") (pintype "passive"))
      (node (ref "R40") (pin "1") (pinfunction "1_1") (pintype "passive"))
      (node (ref "R42") (pin "1") (pinfunction "1_1") (pintype "passive"))
      (node (ref "R44") (pin "1") (pinfunction "1_1") (pintype "passive"))
      (node (ref "R46") (pin "1") (pinfunction "1_1") (pintype "passive"))
      (node (ref "R48") (pin "1") (pinfunction "1_1") (pintype "passive"))
      (node (ref "R50") (pin "1") (pinfunction "1_1") (pintype "passive"))
      (node (ref "R52") (pin "1") (pinfunction "1_1") (pintype "passive"))
      (node (ref "R54") (pin "1") (pinfunction "1_1") (pintype "passive"))
      (node (ref "R56") (pin "1") (pinfunction "1_1") (pintype "passive"))
      (node (ref "R58") (pin "1") (pinfunction "1_1") (pintype "passive"))
      (node (ref "R6") (pin "1") (pinfunction "1_1") (pintype "passive"))
      (node (ref "R60") (pin "1") (pinfunction "1_1") (pintype "passive"))
      (node (ref "R62") (pin "1") (pinfunction "1_1") (pintype "passive"))
      (node (ref "R64") (pin "1") (pinfunction "1_1") (pintype "passive"))
      (node (ref "R66") (pin "1") (pinfunction "1_1") (pintype "passive"))
      (node (ref "R68") (pin "2") (pinfunction "2_2") (pintype "passive"))
      (node (ref "R70") (pin "2") (pinfunction "2_2") (pintype "passive"))
      (node (ref "R72") (pin "2") (pinfunction "2_2") (pintype "passive"))
      (node (ref "R74") (pin "2") (pinfunction "2_2") (pintype "passive"))
      (node (ref "R8") (pin "1") (pinfunction "1_1") (pintype "passive"))
      (node (ref "R82") (pin "1") (pinfunction "1_1") (pintype "passive"))
      (node (ref "R86") (pin "1") (pinfunction "1_1") (pintype "passive"))
      (node (ref "R88") (pin "1") (pinfunction "1_1") (pintype "passive"))
      (node (ref "R90") (pin "1") (pinfunction "1_1") (pintype "passive"))
      (node (ref "R92") (pin "1") (pinfunction "1_1") (pintype "passive"))
      (node (ref "R96") (pin "1") (pinfunction "1_1") (pintype "passive"))
      (node (ref "R98") (pin "1") (pinfunction "1_1") (pintype "passive"))
      (node (ref "U1") (pin "3") (pinfunction "IN_3") (pintype "input"))
      (node (ref "X1") (pin "4") (pinfunction "4_4") (pintype "passive"))
      (node (ref "X2") (pin "4") (pinfunction "4_4") (pintype "passive"))
      (node (ref "X22") (pin "1") (pinfunction "1_1") (pintype "passive"))
      (node (ref "X3") (pin "4") (pinfunction "4_4") (pintype "passive"))
      (node (ref "X4") (pin "4") (pinfunction "4_4") (pintype "passive"))
      (node (ref "X5") (pin "4") (pinfunction "4_4") (pintype "passive"))
      (node (ref "X6") (pin "4") (pinfunction "4_4") (pintype "passive"))
    )
    (net (code "3") (name "ADC0") (class "Default")
      (node (ref "IC4") (pin "1") (pinfunction "CH0_1") (pintype "bidirectional"))
      (node (ref "X12") (pin "2") (pinfunction "2_2") (pintype "passive"))
    )
    (net (code "4") (name "ADC1") (class "Default")
      (node (ref "IC4") (pin "2") (pinfunction "CH1_2") (pintype "bidirectional"))
      (node (ref "X25") (pin "2") (pinfunction "2_2") (pintype "passive"))
    )
    (net (code "5") (name "ADC2") (class "Default")
      (node (ref "IC4") (pin "3") (pinfunction "CH2_3") (pintype "bidirectional"))
      (node (ref "X7") (pin "2") (pinfunction "2_2") (pintype "passive"))
    )
    (net (code "6") (name "ADC3") (class "Default")
      (node (ref "IC4") (pin "4") (pinfunction "CH3_4") (pintype "bidirectional"))
      (node (ref "X23") (pin "2") (pinfunction "2_2") (pintype "passive"))
    )
    (net (code "7") (name "ADC4") (class "Default")
      (node (ref "IC4") (pin "5") (pinfunction "CH4_5") (pintype "bidirectional"))
      (node (ref "X10") (pin "2") (pinfunction "2_2") (pintype "passive"))
    )
    (net (code "8") (name "ADC5") (class "Default")
      (node (ref "IC4") (pin "6") (pinfunction "CH5_6") (pintype "bidirectional"))
      (node (ref "X18") (pin "2") (pinfunction "2_2") (pintype "passive"))
    )
    (net (code "9") (name "ADC6") (class "Default")
      (node (ref "IC4") (pin "7") (pinfunction "CH6_7") (pintype "bidirectional"))
      (node (ref "X20") (pin "2") (pinfunction "2_2") (pintype "passive"))
    )
    (net (code "10") (name "ADC7") (class "Default")
      (node (ref "IC4") (pin "8") (pinfunction "CH7_8") (pintype "bidirectional"))
      (node (ref "X21") (pin "2") (pinfunction "2_2") (pintype "passive"))
    )
    (net (code "11") (name "CANH") (class "Default")
      (node (ref "IC2") (pin "7") (pinfunction "CANH_7") (pintype "bidirectional"))
      (node (ref "J1") (pin "2") (pinfunction "2_2") (pintype "bidirectional"))
      (node (ref "J1") (pin "6") (pinfunction "6_6") (pintype "bidirectional"))
      (node (ref "J2") (pin "2") (pinfunction "2_2") (pintype "bidirectional"))
      (node (ref "J2") (pin "6") (pinfunction "6_6") (pintype "bidirectional"))
      (node (ref "R5") (pin "2") (pinfunction "2_2") (pintype "passive"))
    )
    (net (code "12") (name "CANL") (class "Default")
      (node (ref "IC2") (pin "6") (pinfunction "CANL_6") (pintype "bidirectional"))
      (node (ref "J1") (pin "3") (pinfunction "3_3") (pintype "bidirectional"))
      (node (ref "J1") (pin "7") (pinfunction "7_7") (pintype "bidirectional"))
      (node (ref "J2") (pin "3") (pinfunction "3_3") (pintype "bidirectional"))
      (node (ref "J2") (pin "7") (pinfunction "7_7") (pintype "bidirectional"))
      (node (ref "R5") (pin "1") (pinfunction "1_1") (pintype "passive"))
    )
    (net (code "13") (name "CAN_RX") (class "Default")
      (node (ref "IC1") (pin "44") (pinfunction "PA11_44") (pintype "bidirectional"))
      (node (ref "IC2") (pin "4") (pinfunction "RXD_4") (pintype "bidirectional"))
      (node (ref "R78") (pin "2") (pinfunction "2_2") (pintype "passive"))
    )
    (net (code "14") (name "CAN_TX") (class "Default")
      (node (ref "IC1") (pin "45") (pinfunction "PA12_45") (pintype "bidirectional"))
      (node (ref "IC2") (pin "1") (pinfunction "TXD_1") (pintype "bidirectional"))
      (node (ref "R77") (pin "2") (pinfunction "2_2") (pintype "passive"))
    )
    (net (code "15") (name "ENCODER1-A") (class "Default")
      (node (ref "IC1") (pin "14") (pinfunction "PA0-WKUP_14") (pintype "bidirectional"))
      (node (ref "R47") (pin "1") (pinfunction "1_1") (pintype "passive"))
      (node (ref "X1") (pin "5") (pinfunction "5_5") (pintype "passive"))
    )
    (net (code "16") (name "ENCODER1-B") (class "Default")
      (node (ref "IC1") (pin "15") (pinfunction "PA1_15") (pintype "bidirectional"))
      (node (ref "R11") (pin "1") (pinfunction "1_1") (pintype "passive"))
      (node (ref "X1") (pin "3") (pinfunction "3_3") (pintype "passive"))
    )
    (net (code "17") (name "ENCODER2-A") (class "Default")
      (node (ref "IC1") (pin "37") (pinfunction "PC6_37") (pintype "bidirectional"))
      (node (ref "R49") (pin "1") (pinfunction "1_1") (pintype "passive"))
      (node (ref "X2") (pin "5") (pinfunction "5_5") (pintype "passive"))
    )
    (net (code "18") (name "ENCODER2-B") (class "Default")
      (node (ref "IC1") (pin "38") (pinfunction "PC7_38") (pintype "bidirectional"))
      (node (ref "R13") (pin "1") (pinfunction "1_1") (pintype "passive"))
      (node (ref "X2") (pin "3") (pinfunction "3_3") (pintype "passive"))
    )
    (net (code "19") (name "ENCODER3-A") (class "Default")
      (node (ref "IC1") (pin "41") (pinfunction "PA8_41") (pintype "bidirectional"))
      (node (ref "R53") (pin "1") (pinfunction "1_1") (pintype "passive"))
      (node (ref "X3") (pin "5") (pinfunction "5_5") (pintype "passive"))
    )
    (net (code "20") (name "ENCODER3-B") (class "Default")
      (node (ref "IC1") (pin "42") (pinfunction "PA9_42") (pintype "bidirectional"))
      (node (ref "R15") (pin "1") (pinfunction "1_1") (pintype "passive"))
      (node (ref "X3") (pin "3") (pinfunction "3_3") (pintype "passive"))
    )
    (net (code "21") (name "ENCODER4-A") (class "Default")
      (node (ref "IC1") (pin "50") (pinfunction "PA15_50") (pintype "bidirectional"))
      (node (ref "R4") (pin "1") (pinfunction "1_1") (pintype "passive"))
      (node (ref "X4") (pin "5") (pinfunction "5_5") (pintype "passive"))
    )
    (net (code "22") (name "ENCODER4-B") (class "Default")
      (node (ref "IC1") (pin "55") (pinfunction "PB3_55") (pintype "bidirectional"))
      (node (ref "R17") (pin "1") (pinfunction "1_1") (pintype "passive"))
      (node (ref "X4") (pin "3") (pinfunction "3_3") (pintype "passive"))
    )
    (net (code "23") (name "ENCODER5-A") (class "Default")
      (node (ref "IC1") (pin "56") (pinfunction "PB4_56") (pintype "bidirectional"))
      (node (ref "R7") (pin "1") (pinfunction "1_1") (pintype "passive"))
      (node (ref "X5") (pin "5") (pinfunction "5_5") (pintype "passive"))
    )
    (net (code "24") (name "ENCODER5-B") (class "Default")
      (node (ref "IC1") (pin "57") (pinfunction "PB5_57") (pintype "bidirectional"))
      (node (ref "R19") (pin "1") (pinfunction "1_1") (pintype "passive"))
      (node (ref "X5") (pin "3") (pinfunction "3_3") (pintype "passive"))
    )
    (net (code "25") (name "ENCODER6-A") (class "Default")
      (node (ref "IC1") (pin "58") (pinfunction "PB6_58") (pintype "bidirectional"))
      (node (ref "R9") (pin "1") (pinfunction "1_1") (pintype "passive"))
      (node (ref "X6") (pin "5") (pinfunction "5_5") (pintype "passive"))
    )
    (net (code "26") (name "ENCODER6-B") (class "Default")
      (node (ref "IC1") (pin "59") (pinfunction "PB7_59") (pintype "bidirectional"))
      (node (ref "R21") (pin "1") (pinfunction "1_1") (pintype "passive"))
      (node (ref "X6") (pin "3") (pinfunction "3_3") (pintype "passive"))
    )
    (net (code "27") (name "GND") (class "Default")
      (node (ref "3V3") (pin "K") (pinfunction "K_K") (pintype "passive"))
      (node (ref "5V") (pin "K") (pinfunction "K_K") (pintype "passive"))
      (node (ref "C1") (pin "1") (pinfunction "1_1") (pintype "bidirectional"))
      (node (ref "C10") (pin "1") (pinfunction "1_1") (pintype "bidirectional"))
      (node (ref "C11") (pin "1") (pinfunction "1_1") (pintype "bidirectional"))
      (node (ref "C12") (pin "1") (pinfunction "1_1") (pintype "bidirectional"))
      (node (ref "C13") (pin "1") (pinfunction "1_1") (pintype "bidirectional"))
      (node (ref "C14") (pin "1") (pinfunction "1_1") (pintype "bidirectional"))
      (node (ref "C15") (pin "1") (pinfunction "1_1") (pintype "bidirectional"))
      (node (ref "C16") (pin "1") (pinfunction "1_1") (pintype "bidirectional"))
      (node (ref "C17") (pin "1") (pinfunction "1_1") (pintype "bidirectional"))
      (node (ref "C18") (pin "1") (pinfunction "1_1") (pintype "bidirectional"))
      (node (ref "C19") (pin "1") (pinfunction "1_1") (pintype "bidirectional"))
      (node (ref "C2") (pin "1") (pinfunction "1_1") (pintype "bidirectional"))
      (node (ref "C20") (pin "1") (pinfunction "1_1") (pintype "bidirectional"))
      (node (ref "C21") (pin "1") (pinfunction "1_1") (pintype "bidirectional"))
      (node (ref "C22") (pin "1") (pinfunction "1_1") (pintype "bidirectional"))
      (node (ref "C23") (pin "1") (pinfunction "1_1") (pintype "bidirectional"))
      (node (ref "C3") (pin "1") (pinfunction "1_1") (pintype "bidirectional"))
      (node (ref "C4") (pin "1") (pinfunction "1_1") (pintype "bidirectional"))
      (node (ref "C5") (pin "1") (pinfunction "1_1") (pintype "bidirectional"))
      (node (ref "C6") (pin "1") (pinfunction "1_1") (pintype "bidirectional"))
      (node (ref "C7") (pin "1") (pinfunction "1_1") (pintype "bidirectional"))
      (node (ref "C8") (pin "1") (pinfunction "1_1") (pintype "bidirectional"))
      (node (ref "C9") (pin "1") (pinfunction "1_1") (pintype "bidirectional"))
      (node (ref "IC1") (pin "12") (pinfunction "VSSA_12") (pintype "power_in"))
      (node (ref "IC1") (pin "18") (pinfunction "VSS_1_18") (pintype "power_in"))
      (node (ref "IC1") (pin "31") (pinfunction "VSS_2_31") (pintype "power_in"))
      (node (ref "IC1") (pin "47") (pinfunction "VSS_3_47") (pintype "power_in"))
      (node (ref "IC1") (pin "63") (pinfunction "VSS_4_63") (pintype "power_in"))
      (node (ref "IC2") (pin "2") (pinfunction "GND_2") (pintype "bidirectional"))
      (node (ref "IC2") (pin "8") (pinfunction "S_8") (pintype "bidirectional"))
      (node (ref "IC4") (pin "14") (pinfunction "AGND_14") (pintype "bidirectional"))
      (node (ref "IC4") (pin "9") (pinfunction "DGND_9") (pintype "bidirectional"))
      (node (ref "J1") (pin "4") (pinfunction "4_4") (pintype "bidirectional"))
      (node (ref "J1") (pin "8") (pinfunction "8_8") (pintype "bidirectional"))
      (node (ref "J2") (pin "4") (pinfunction "4_4") (pintype "bidirectional"))
      (node (ref "J2") (pin "8") (pinfunction "8_8") (pintype "bidirectional"))
      (node (ref "Q10") (pin "2") (pinfunction "S_2") (pintype "bidirectional"))
      (node (ref "Q9") (pin "2") (pinfunction "S_2") (pintype "bidirectional"))
      (node (ref "R1") (pin "2") (pinfunction "2_2") (pintype "passive"))
      (node (ref "S2") (pin "C1") (pinfunction "COM_1_C1") (pintype "bidirectional"))
      (node (ref "S2") (pin "D1") (pinfunction "COM_2_D1") (pintype "bidirectional"))
      (node (ref "SL1") (pin "3") (pinfunction "3_3") (pintype "passive"))
      (node (ref "TR1") (pin "2") (pinfunction "S_2") (pintype "bidirectional"))
      (node (ref "TR10") (pin "2") (pinfunction "S_2") (pintype "bidirectional"))
      (node (ref "TR11") (pin "2") (pinfunction "S_2") (pintype "bidirectional"))
      (node (ref "TR12") (pin "2") (pinfunction "S_2") (pintype "bidirectional"))
      (node (ref "TR13") (pin "2") (pinfunction "S_2") (pintype "bidirectional"))
      (node (ref "TR14") (pin "2") (pinfunction "S_2") (pintype "bidirectional"))
      (node (ref "TR15") (pin "2") (pinfunction "S_2") (pintype "bidirectional"))
      (node (ref "TR16") (pin "2") (pinfunction "S_2") (pintype "bidirectional"))
      (node (ref "TR17") (pin "2") (pinfunction "S_2") (pintype "bidirectional"))
      (node (ref "TR2") (pin "2") (pinfunction "S_2") (pintype "bidirectional"))
      (node (ref "TR21") (pin "2") (pinfunction "S_2") (pintype "bidirectional"))
      (node (ref "TR3") (pin "2") (pinfunction "S_2") (pintype "bidirectional"))
      (node (ref "TR4") (pin "2") (pinfunction "S_2") (pintype "bidirectional"))
      (node (ref "TR5") (pin "2") (pinfunction "S_2") (pintype "bidirectional"))
      (node (ref "TR6") (pin "2") (pinfunction "S_2") (pintype "bidirectional"))
      (node (ref "TR7") (pin "2") (pinfunction "S_2") (pintype "bidirectional"))
      (node (ref "TR8") (pin "2") (pinfunction "S_2") (pintype "bidirectional"))
      (node (ref "TR9") (pin "2") (pinfunction "S_2") (pintype "bidirectional"))
      (node (ref "U1") (pin "1") (pinfunction "GND_1") (pintype "passive"))
      (node (ref "X1") (pin "1") (pinfunction "1_1") (pintype "passive"))
      (node (ref "X10") (pin "3") (pinfunction "3_3") (pintype "passive"))
      (node (ref "X12") (pin "3") (pinfunction "3_3") (pintype "passive"))
      (node (ref "X14") (pin "4") (pinfunction "4_4") (pintype "passive"))
      (node (ref "X17") (pin "4") (pinfunction "4_4") (pintype "passive"))
      (node (ref "X18") (pin "3") (pinfunction "3_3") (pintype "passive"))
      (node (ref "X2") (pin "1") (pinfunction "1_1") (pintype "passive"))
      (node (ref "X20") (pin "3") (pinfunction "3_3") (pintype "passive"))
      (node (ref "X21") (pin "3") (pinfunction "3_3") (pintype "passive"))
      (node (ref "X22") (pin "3") (pinfunction "3_3") (pintype "passive"))
      (node (ref "X23") (pin "3") (pinfunction "3_3") (pintype "passive"))
      (node (ref "X24") (pin "3") (pinfunction "3_3") (pintype "passive"))
      (node (ref "X25") (pin "3") (pinfunction "3_3") (pintype "passive"))
      (node (ref "X27") (pin "3") (pinfunction "3_3") (pintype "passive"))
      (node (ref "X28") (pin "3") (pinfunction "3_3") (pintype "passive"))
      (node (ref "X29") (pin "3") (pinfunction "3_3") (pintype "passive"))
      (node (ref "X3") (pin "1") (pinfunction "1_1") (pintype "passive"))
      (node (ref "X30") (pin "3") (pinfunction "3_3") (pintype "passive"))
      (node (ref "X32") (pin "3") (pinfunction "3_3") (pintype "passive"))
      (node (ref "X33") (pin "3") (pinfunction "3_3") (pintype "passive"))
      (node (ref "X34") (pin "3") (pinfunction "3_3") (pintype "passive"))
      (node (ref "X35") (pin "3") (pinfunction "3_3") (pintype "passive"))
      (node (ref "X4") (pin "1") (pinfunction "1_1") (pintype "passive"))
      (node (ref "X5") (pin "1") (pinfunction "1_1") (pintype "passive"))
      (node (ref "X6") (pin "1") (pinfunction "1_1") (pintype "passive"))
      (node (ref "X7") (pin "3") (pinfunction "3_3") (pintype "passive"))
      (node (ref "X9") (pin "4") (pinfunction "4_4") (pintype "passive"))
    )
    (net (code "28") (name "MISO_5V") (class "Default")
      (node (ref "IC4") (pin "12") (pinfunction "DOUT_12") (pintype "bidirectional"))
      (node (ref "Q3") (pin "3") (pinfunction "D_3") (pintype "bidirectional"))
      (node (ref "R28") (pin "2") (pinfunction "2_2") (pintype "passive"))
    )
    (net (code "29") (name "MOSI_5V") (class "Default")
      (node (ref "IC4") (pin "11") (pinfunction "DIN_11") (pintype "bidirectional"))
      (node (ref "Q2") (pin "3") (pinfunction "D_3") (pintype "bidirectional"))
      (node (ref "R26") (pin "2") (pinfunction "2_2") (pintype "passive"))
    )
    (net (code "30") (name "NRST") (class "Default")
      (node (ref "C23") (pin "2") (pinfunction "2_2") (pintype "bidirectional"))
      (node (ref "IC1") (pin "7") (pinfunction "NRST_7") (pintype "bidirectional"))
      (node (ref "S2") (pin "A1") (pinfunction "NO_1_A1") (pintype "bidirectional"))
      (node (ref "SL1") (pin "5") (pinfunction "5_5") (pintype "passive"))
    )
    (net (code "31") (name "NSS_5V") (class "Default")
      (node (ref "IC4") (pin "10") (pinfunction "~{CS}/SHDN_10") (pintype "bidirectional"))
      (node (ref "Q1") (pin "3") (pinfunction "D_3") (pintype "bidirectional"))
      (node (ref "R24") (pin "2") (pinfunction "2_2") (pintype "passive"))
    )
    (net (code "32") (name "Net-(1-A-PadA)") (class "Default")
      (node (ref "1-A") (pin "A") (pinfunction "A_A") (pintype "passive"))
      (node (ref "R48") (pin "2") (pinfunction "2_2") (pintype "passive"))
    )
    (net (code "33") (name "Net-(1-B-PadA)") (class "Default")
      (node (ref "1-B") (pin "A") (pinfunction "A_A") (pintype "passive"))
      (node (ref "R12") (pin "1") (pinfunction "1_1") (pintype "passive"))
    )
    (net (code "34") (name "Net-(2-A-PadA)") (class "Default")
      (node (ref "2-A") (pin "A") (pinfunction "A_A") (pintype "passive"))
      (node (ref "R50") (pin "2") (pinfunction "2_2") (pintype "passive"))
    )
    (net (code "35") (name "Net-(2-B-PadA)") (class "Default")
      (node (ref "2-B") (pin "A") (pinfunction "A_A") (pintype "passive"))
      (node (ref "R14") (pin "2") (pinfunction "2_2") (pintype "passive"))
    )
    (net (code "36") (name "Net-(3-A-PadA)") (class "Default")
      (node (ref "3-A") (pin "A") (pinfunction "A_A") (pintype "passive"))
      (node (ref "R54") (pin "2") (pinfunction "2_2") (pintype "passive"))
    )
    (net (code "37") (name "Net-(3-B-PadA)") (class "Default")
      (node (ref "3-B") (pin "A") (pinfunction "A_A") (pintype "passive"))
      (node (ref "R16") (pin "2") (pinfunction "2_2") (pintype "passive"))
    )
    (net (code "38") (name "Net-(3V3-PadA)") (class "Default")
      (node (ref "3V3") (pin "A") (pinfunction "A_A") (pintype "passive"))
      (node (ref "R2") (pin "2") (pinfunction "2_2") (pintype "passive"))
    )
    (net (code "39") (name "Net-(4-A-PadA)") (class "Default")
      (node (ref "4-A") (pin "A") (pinfunction "A_A") (pintype "passive"))
      (node (ref "R6") (pin "2") (pinfunction "2_2") (pintype "passive"))
    )
    (net (code "40") (name "Net-(4-B-PadA)") (class "Default")
      (node (ref "4-B") (pin "A") (pinfunction "A_A") (pintype "passive"))
      (node (ref "R18") (pin "2") (pinfunction "2_2") (pintype "passive"))
    )
    (net (code "41") (name "Net-(5-A-PadA)") (class "Default")
      (node (ref "5-A") (pin "A") (pinfunction "A_A") (pintype "passive"))
      (node (ref "R8") (pin "2") (pinfunction "2_2") (pintype "passive"))
    )
    (net (code "42") (name "Net-(5-B-PadA)") (class "Default")
      (node (ref "5-B") (pin "A") (pinfunction "A_A") (pintype "passive"))
      (node (ref "R20") (pin "2") (pinfunction "2_2") (pintype "passive"))
    )
    (net (code "43") (name "Net-(5V-PadA)") (class "Default")
      (node (ref "5V") (pin "A") (pinfunction "A_A") (pintype "passive"))
      (node (ref "R3") (pin "2") (pinfunction "2_2") (pintype "passive"))
    )
    (net (code "44") (name "Net-(6-A-PadA)") (class "Default")
      (node (ref "6-A") (pin "A") (pinfunction "A_A") (pintype "passive"))
      (node (ref "R10") (pin "2") (pinfunction "2_2") (pintype "passive"))
    )
    (net (code "45") (name "Net-(6-B-PadA)") (class "Default")
      (node (ref "6-B") (pin "A") (pinfunction "A_A") (pintype "passive"))
      (node (ref "R22") (pin "2") (pinfunction "2_2") (pintype "passive"))
    )
    (net (code "46") (name "Net-(CAN_RX-PadK)") (class "Default")
      (node (ref "CAN_RX") (pin "K") (pinfunction "K_K") (pintype "passive"))
      (node (ref "R76") (pin "1") (pinfunction "1_1") (pintype "passive"))
    )
    (net (code "47") (name "Net-(CAN_TX-PadK)") (class "Default")
      (node (ref "CAN_TX") (pin "K") (pinfunction "K_K") (pintype "passive"))
      (node (ref "R75") (pin "1") (pinfunction "1_1") (pintype "passive"))
    )
    (net (code "48") (name "Net-(IC1-BOOT0)") (class "Default")
      (node (ref "IC1") (pin "60") (pinfunction "BOOT0_60") (pintype "bidirectional"))
      (node (ref "R1") (pin "1") (pinfunction "1_1") (pintype "passive"))
    )
    (net (code "49") (name "Net-(PA10-PadA)") (class "Default")
      (node (ref "PA10") (pin "A") (pinfunction "A_A") (pintype "passive"))
      (node (ref "R60") (pin "2") (pinfunction "2_2") (pintype "passive"))
    )
    (net (code "50") (name "Net-(PB2-PadA)") (class "Default")
      (node (ref "PB2") (pin "A") (pinfunction "A_A") (pintype "passive"))
      (node (ref "R66") (pin "2") (pinfunction "2_2") (pintype "passive"))
    )
    (net (code "51") (name "Net-(PC8-PadA)") (class "Default")
      (node (ref "PC8") (pin "A") (pinfunction "A_A") (pintype "passive"))
      (node (ref "R64") (pin "2") (pinfunction "2_2") (pintype "passive"))
    )
    (net (code "52") (name "Net-(PC9-PadA)") (class "Default")
      (node (ref "PC9") (pin "A") (pinfunction "A_A") (pintype "passive"))
      (node (ref "R62") (pin "2") (pinfunction "2_2") (pintype "passive"))
    )
    (net (code "53") (name "Net-(Q9-D)") (class "Default")
      (node (ref "Q9") (pin "3") (pinfunction "D_3") (pintype "bidirectional"))
      (node (ref "R75") (pin "2") (pinfunction "2_2") (pintype "passive"))
    )
    (net (code "54") (name "Net-(Q9-G)") (class "Default")
      (node (ref "Q9") (pin "1") (pinfunction "G_1") (pintype "bidirectional"))
      (node (ref "R77") (pin "1") (pinfunction "1_1") (pintype "passive"))
    )
    (net (code "55") (name "Net-(Q10-D)") (class "Default")
      (node (ref "Q10") (pin "3") (pinfunction "D_3") (pintype "bidirectional"))
      (node (ref "R76") (pin "2") (pinfunction "2_2") (pintype "passive"))
    )
    (net (code "56") (name "Net-(Q10-G)") (class "Default")
      (node (ref "Q10") (pin "1") (pinfunction "G_1") (pintype "bidirectional"))
      (node (ref "R78") (pin "1") (pinfunction "1_1") (pintype "passive"))
    )
    (net (code "57") (name "Net-(R31-Pad1)") (class "Default")
      (node (ref "R31") (pin "1") (pinfunction "1_1") (pintype "passive"))
      (node (ref "R32") (pin "1") (pinfunction "1_1") (pintype "passive"))
      (node (ref "X9") (pin "1") (pinfunction "1_1") (pintype "passive"))
    )
    (net (code "58") (name "Net-(R33-Pad2)") (class "Default")
      (node (ref "R33") (pin "2") (pinfunction "2_2") (pintype "passive"))
      (node (ref "R34") (pin "2") (pinfunction "2_2") (pintype "passive"))
      (node (ref "X25") (pin "1") (pinfunction "1_1") (pintype "passive"))
    )
    (net (code "59") (name "Net-(R35-Pad2)") (class "Default")
      (node (ref "R35") (pin "2") (pinfunction "2_2") (pintype "passive"))
      (node (ref "R36") (pin "2") (pinfunction "2_2") (pintype "passive"))
      (node (ref "X12") (pin "1") (pinfunction "1_1") (pintype "passive"))
    )
    (net (code "60") (name "Net-(R37-Pad2)") (class "Default")
      (node (ref "R37") (pin "2") (pinfunction "2_2") (pintype "passive"))
      (node (ref "R38") (pin "2") (pinfunction "2_2") (pintype "passive"))
      (node (ref "X7") (pin "1") (pinfunction "1_1") (pintype "passive"))
    )
    (net (code "61") (name "Net-(R39-Pad2)") (class "Default")
      (node (ref "R39") (pin "2") (pinfunction "2_2") (pintype "passive"))
      (node (ref "R40") (pin "2") (pinfunction "2_2") (pintype "passive"))
      (node (ref "X23") (pin "1") (pinfunction "1_1") (pintype "passive"))
    )
    (net (code "62") (name "Net-(R41-Pad2)") (class "Default")
      (node (ref "R41") (pin "2") (pinfunction "2_2") (pintype "passive"))
      (node (ref "R42") (pin "2") (pinfunction "2_2") (pintype "passive"))
      (node (ref "X10") (pin "1") (pinfunction "1_1") (pintype "passive"))
    )
    (net (code "63") (name "Net-(R43-Pad2)") (class "Default")
      (node (ref "R43") (pin "2") (pinfunction "2_2") (pintype "passive"))
      (node (ref "R44") (pin "2") (pinfunction "2_2") (pintype "passive"))
      (node (ref "X18") (pin "1") (pinfunction "1_1") (pintype "passive"))
    )
    (net (code "64") (name "Net-(R45-Pad2)") (class "Default")
      (node (ref "R45") (pin "2") (pinfunction "2_2") (pintype "passive"))
      (node (ref "R46") (pin "2") (pinfunction "2_2") (pintype "passive"))
      (node (ref "X20") (pin "1") (pinfunction "1_1") (pintype "passive"))
    )
    (net (code "65") (name "Net-(R51-Pad2)") (class "Default")
      (node (ref "R51") (pin "2") (pinfunction "2_2") (pintype "passive"))
      (node (ref "R52") (pin "2") (pinfunction "2_2") (pintype "passive"))
      (node (ref "X21") (pin "1") (pinfunction "1_1") (pintype "passive"))
    )
    (net (code "66") (name "Net-(R56-Pad2)") (class "Default")
      (node (ref "R56") (pin "2") (pinfunction "2_2") (pintype "passive"))
      (node (ref "TX") (pin "A") (pinfunction "A_A") (pintype "passive"))
    )
    (net (code "67") (name "Net-(R58-Pad2)") (class "Default")
      (node (ref "R58") (pin "2") (pinfunction "2_2") (pintype "passive"))
      (node (ref "RX") (pin "A") (pinfunction "A_A") (pintype "passive"))
    )
    (net (code "68") (name "Net-(R67-Pad1)") (class "Default")
      (node (ref "R67") (pin "1") (pinfunction "1_1") (pintype "passive"))
      (node (ref "R68") (pin "1") (pinfunction "1_1") (pintype "passive"))
      (node (ref "X17") (pin "1") (pinfunction "1_1") (pintype "passive"))
    )
    (net (code "69") (name "Net-(R69-Pad1)") (class "Default")
      (node (ref "R69") (pin "1") (pinfunction "1_1") (pintype "passive"))
      (node (ref "R70") (pin "1") (pinfunction "1_1") (pintype "passive"))
      (node (ref "X14") (pin "1") (pinfunction "1_1") (pintype "passive"))
    )
    (net (code "70") (name "Net-(R71-Pad1)") (class "Default")
      (node (ref "R71") (pin "1") (pinfunction "1_1") (pintype "passive"))
      (node (ref "R72") (pin "1") (pinfunction "1_1") (pintype "passive"))
      (node (ref "X13") (pin "1") (pinfunction "1_1") (pintype "passive"))
    )
    (net (code "71") (name "Net-(R73-Pad1)") (class "Default")
      (node (ref "R73") (pin "1") (pinfunction "1_1") (pintype "passive"))
      (node (ref "R74") (pin "1") (pinfunction "1_1") (pintype "passive"))
      (node (ref "X11") (pin "1") (pinfunction "1_1") (pintype "passive"))
    )
    (net (code "72") (name "Net-(R81-Pad2)") (class "Default")
      (node (ref "R81") (pin "2") (pinfunction "2_2") (pintype "passive"))
      (node (ref "R82") (pin "2") (pinfunction "2_2") (pintype "passive"))
      (node (ref "X24") (pin "1") (pinfunction "1_1") (pintype "passive"))
    )
    (net (code "73") (name "Net-(R85-Pad2)") (class "Default")
      (node (ref "R85") (pin "2") (pinfunction "2_2") (pintype "passive"))
      (node (ref "R86") (pin "2") (pinfunction "2_2") (pintype "passive"))
      (node (ref "X27") (pin "1") (pinfunction "1_1") (pintype "passive"))
    )
    (net (code "74") (name "Net-(R87-Pad2)") (class "Default")
      (node (ref "R87") (pin "2") (pinfunction "2_2") (pintype "passive"))
      (node (ref "R88") (pin "2") (pinfunction "2_2") (pintype "passive"))
      (node (ref "X28") (pin "1") (pinfunction "1_1") (pintype "passive"))
    )
    (net (code "75") (name "Net-(R89-Pad2)") (class "Default")
      (node (ref "R89") (pin "2") (pinfunction "2_2") (pintype "passive"))
      (node (ref "R90") (pin "2") (pinfunction "2_2") (pintype "passive"))
      (node (ref "X29") (pin "1") (pinfunction "1_1") (pintype "passive"))
    )
    (net (code "76") (name "Net-(R91-Pad2)") (class "Default")
      (node (ref "R91") (pin "2") (pinfunction "2_2") (pintype "passive"))
      (node (ref "R92") (pin "2") (pinfunction "2_2") (pintype "passive"))
      (node (ref "X30") (pin "1") (pinfunction "1_1") (pintype "passive"))
    )
    (net (code "77") (name "Net-(R95-Pad2)") (class "Default")
      (node (ref "R95") (pin "2") (pinfunction "2_2") (pintype "passive"))
      (node (ref "R96") (pin "2") (pinfunction "2_2") (pintype "passive"))
      (node (ref "X32") (pin "1") (pinfunction "1_1") (pintype "passive"))
    )
    (net (code "78") (name "Net-(R97-Pad2)") (class "Default")
      (node (ref "R97") (pin "2") (pinfunction "2_2") (pintype "passive"))
      (node (ref "R98") (pin "2") (pinfunction "2_2") (pintype "passive"))
      (node (ref "X33") (pin "1") (pinfunction "1_1") (pintype "passive"))
    )
    (net (code "79") (name "Net-(R100-Pad2)") (class "Default")
      (node (ref "R100") (pin "2") (pinfunction "2_2") (pintype "passive"))
      (node (ref "R99") (pin "2") (pinfunction "2_2") (pintype "passive"))
      (node (ref "X34") (pin "1") (pinfunction "1_1") (pintype "passive"))
    )
    (net (code "80") (name "Net-(R101-Pad2)") (class "Default")
      (node (ref "R101") (pin "2") (pinfunction "2_2") (pintype "passive"))
      (node (ref "R102") (pin "2") (pinfunction "2_2") (pintype "passive"))
      (node (ref "X35") (pin "1") (pinfunction "1_1") (pintype "passive"))
    )
    (net (code "81") (name "Net-(TR1-D)") (class "Default")
      (node (ref "4-A") (pin "K") (pinfunction "K_K") (pintype "passive"))
      (node (ref "TR1") (pin "3") (pinfunction "D_3") (pintype "bidirectional"))
    )
    (net (code "82") (name "Net-(TR1-G)") (class "Default")
      (node (ref "R4") (pin "2") (pinfunction "2_2") (pintype "passive"))
      (node (ref "TR1") (pin "1") (pinfunction "G_1") (pintype "bidirectional"))
    )
    (net (code "83") (name "Net-(TR2-D)") (class "Default")
      (node (ref "5-A") (pin "K") (pinfunction "K_K") (pintype "passive"))
      (node (ref "TR2") (pin "3") (pinfunction "D_3") (pintype "bidirectional"))
    )
    (net (code "84") (name "Net-(TR2-G)") (class "Default")
      (node (ref "R7") (pin "2") (pinfunction "2_2") (pintype "passive"))
      (node (ref "TR2") (pin "1") (pinfunction "G_1") (pintype "bidirectional"))
    )
    (net (code "85") (name "Net-(TR3-D)") (class "Default")
      (node (ref "6-A") (pin "K") (pinfunction "K_K") (pintype "passive"))
      (node (ref "TR3") (pin "3") (pinfunction "D_3") (pintype "bidirectional"))
    )
    (net (code "86") (name "Net-(TR3-G)") (class "Default")
      (node (ref "R9") (pin "2") (pinfunction "2_2") (pintype "passive"))
      (node (ref "TR3") (pin "1") (pinfunction "G_1") (pintype "bidirectional"))
    )
    (net (code "87") (name "Net-(TR4-D)") (class "Default")
      (node (ref "1-B") (pin "K") (pinfunction "K_K") (pintype "passive"))
      (node (ref "TR4") (pin "3") (pinfunction "D_3") (pintype "bidirectional"))
    )
    (net (code "88") (name "Net-(TR4-G)") (class "Default")
      (node (ref "R11") (pin "2") (pinfunction "2_2") (pintype "passive"))
      (node (ref "TR4") (pin "1") (pinfunction "G_1") (pintype "bidirectional"))
    )
    (net (code "89") (name "Net-(TR5-D)") (class "Default")
      (node (ref "2-B") (pin "K") (pinfunction "K_K") (pintype "passive"))
      (node (ref "TR5") (pin "3") (pinfunction "D_3") (pintype "bidirectional"))
    )
    (net (code "90") (name "Net-(TR5-G)") (class "Default")
      (node (ref "R13") (pin "2") (pinfunction "2_2") (pintype "passive"))
      (node (ref "TR5") (pin "1") (pinfunction "G_1") (pintype "bidirectional"))
    )
    (net (code "91") (name "Net-(TR6-D)") (class "Default")
      (node (ref "3-B") (pin "K") (pinfunction "K_K") (pintype "passive"))
      (node (ref "TR6") (pin "3") (pinfunction "D_3") (pintype "bidirectional"))
    )
    (net (code "92") (name "Net-(TR6-G)") (class "Default")
      (node (ref "R15") (pin "2") (pinfunction "2_2") (pintype "passive"))
      (node (ref "TR6") (pin "1") (pinfunction "G_1") (pintype "bidirectional"))
    )
    (net (code "93") (name "Net-(TR7-D)") (class "Default")
      (node (ref "4-B") (pin "K") (pinfunction "K_K") (pintype "passive"))
      (node (ref "TR7") (pin "3") (pinfunction "D_3") (pintype "bidirectional"))
    )
    (net (code "94") (name "Net-(TR7-G)") (class "Default")
      (node (ref "R17") (pin "2") (pinfunction "2_2") (pintype "passive"))
      (node (ref "TR7") (pin "1") (pinfunction "G_1") (pintype "bidirectional"))
    )
    (net (code "95") (name "Net-(TR8-D)") (class "Default")
      (node (ref "5-B") (pin "K") (pinfunction "K_K") (pintype "passive"))
      (node (ref "TR8") (pin "3") (pinfunction "D_3") (pintype "bidirectional"))
    )
    (net (code "96") (name "Net-(TR8-G)") (class "Default")
      (node (ref "R19") (pin "2") (pinfunction "2_2") (pintype "passive"))
      (node (ref "TR8") (pin "1") (pinfunction "G_1") (pintype "bidirectional"))
    )
    (net (code "97") (name "Net-(TR9-D)") (class "Default")
      (node (ref "6-B") (pin "K") (pinfunction "K_K") (pintype "passive"))
      (node (ref "TR9") (pin "3") (pinfunction "D_3") (pintype "bidirectional"))
    )
    (net (code "98") (name "Net-(TR9-G)") (class "Default")
      (node (ref "R21") (pin "2") (pinfunction "2_2") (pintype "passive"))
      (node (ref "TR9") (pin "1") (pinfunction "G_1") (pintype "bidirectional"))
    )
    (net (code "99") (name "Net-(TR10-D)") (class "Default")
      (node (ref "TR10") (pin "3") (pinfunction "D_3") (pintype "bidirectional"))
      (node (ref "TX") (pin "K") (pinfunction "K_K") (pintype "passive"))
    )
    (net (code "100") (name "Net-(TR10-G)") (class "Default")
      (node (ref "R55") (pin "2") (pinfunction "2_2") (pintype "passive"))
      (node (ref "TR10") (pin "1") (pinfunction "G_1") (pintype "bidirectional"))
    )
    (net (code "101") (name "Net-(TR11-D)") (class "Default")
      (node (ref "RX") (pin "K") (pinfunction "K_K") (pintype "passive"))
      (node (ref "TR11") (pin "3") (pinfunction "D_3") (pintype "bidirectional"))
    )
    (net (code "102") (name "Net-(TR11-G)") (class "Default")
      (node (ref "R57") (pin "2") (pinfunction "2_2") (pintype "passive"))
      (node (ref "TR11") (pin "1") (pinfunction "G_1") (pintype "bidirectional"))
    )
    (net (code "103") (name "Net-(TR12-D)") (class "Default")
      (node (ref "PA10") (pin "K") (pinfunction "K_K") (pintype "passive"))
      (node (ref "TR12") (pin "3") (pinfunction "D_3") (pintype "bidirectional"))
    )
    (net (code "104") (name "Net-(TR12-G)") (class "Default")
      (node (ref "R59") (pin "2") (pinfunction "2_2") (pintype "passive"))
      (node (ref "TR12") (pin "1") (pinfunction "G_1") (pintype "bidirectional"))
    )
    (net (code "105") (name "Net-(TR13-D)") (class "Default")
      (node (ref "PC9") (pin "K") (pinfunction "K_K") (pintype "passive"))
      (node (ref "TR13") (pin "3") (pinfunction "D_3") (pintype "bidirectional"))
    )
    (net (code "106") (name "Net-(TR13-G)") (class "Default")
      (node (ref "R61") (pin "2") (pinfunction "2_2") (pintype "passive"))
      (node (ref "TR13") (pin "1") (pinfunction "G_1") (pintype "bidirectional"))
    )
    (net (code "107") (name "Net-(TR14-D)") (class "Default")
      (node (ref "PC8") (pin "K") (pinfunction "K_K") (pintype "passive"))
      (node (ref "TR14") (pin "3") (pinfunction "D_3") (pintype "bidirectional"))
    )
    (net (code "108") (name "Net-(TR14-G)") (class "Default")
      (node (ref "R63") (pin "2") (pinfunction "2_2") (pintype "passive"))
      (node (ref "TR14") (pin "1") (pinfunction "G_1") (pintype "bidirectional"))
    )
    (net (code "109") (name "Net-(TR15-D)") (class "Default")
      (node (ref "1-A") (pin "K") (pinfunction "K_K") (pintype "passive"))
      (node (ref "TR15") (pin "3") (pinfunction "D_3") (pintype "bidirectional"))
    )
    (net (code "110") (name "Net-(TR15-G)") (class "Default")
      (node (ref "R47") (pin "2") (pinfunction "2_2") (pintype "passive"))
      (node (ref "TR15") (pin "1") (pinfunction "G_1") (pintype "bidirectional"))
    )
    (net (code "111") (name "Net-(TR16-D)") (class "Default")
      (node (ref "2-A") (pin "K") (pinfunction "K_K") (pintype "passive"))
      (node (ref "TR16") (pin "3") (pinfunction "D_3") (pintype "bidirectional"))
    )
    (net (code "112") (name "Net-(TR16-G)") (class "Default")
      (node (ref "R49") (pin "2") (pinfunction "2_2") (pintype "passive"))
      (node (ref "TR16") (pin "1") (pinfunction "G_1") (pintype "bidirectional"))
    )
    (net (code "113") (name "Net-(TR17-D)") (class "Default")
      (node (ref "PB2") (pin "K") (pinfunction "K_K") (pintype "passive"))
      (node (ref "TR17") (pin "3") (pinfunction "D_3") (pintype "bidirectional"))
    )
    (net (code "114") (name "Net-(TR17-G)") (class "Default")
      (node (ref "R65") (pin "2") (pinfunction "2_2") (pintype "passive"))
      (node (ref "TR17") (pin "1") (pinfunction "G_1") (pintype "bidirectional"))
    )
    (net (code "115") (name "Net-(TR21-D)") (class "Default")
      (node (ref "3-A") (pin "K") (pinfunction "K_K") (pintype "passive"))
      (node (ref "TR21") (pin "3") (pinfunction "D_3") (pintype "bidirectional"))
    )
    (net (code "116") (name "Net-(TR21-G)") (class "Default")
      (node (ref "R53") (pin "2") (pinfunction "2_2") (pintype "passive"))
      (node (ref "TR21") (pin "1") (pinfunction "G_1") (pintype "bidirectional"))
    )
    (net (code "117") (name "PA10") (class "Default")
      (node (ref "IC1") (pin "43") (pinfunction "PA10_43") (pintype "bidirectional"))
      (node (ref "R59") (pin "1") (pinfunction "1_1") (pintype "passive"))
    )
    (net (code "118") (name "PB0") (class "Default")
      (node (ref "IC1") (pin "25") (pinfunction "PB0_25") (pintype "bidirectional"))
      (node (ref "X29") (pin "2") (pinfunction "2_2") (pintype "passive"))
    )
    (net (code "119") (name "PB1") (class "Default")
      (node (ref "IC1") (pin "26") (pinfunction "PB1_26") (pintype "bidirectional"))
      (node (ref "X30") (pin "2") (pinfunction "2_2") (pintype "passive"))
    )
    (net (code "120") (name "PB2") (class "Default")
      (node (ref "IC1") (pin "27") (pinfunction "PB2_27") (pintype "bidirectional"))
      (node (ref "R65") (pin "1") (pinfunction "1_1") (pintype "passive"))
    )
    (net (code "121") (name "PC1") (class "Default")
      (node (ref "IC1") (pin "9") (pinfunction "PC1_9") (pintype "bidirectional"))
      (node (ref "X24") (pin "2") (pinfunction "2_2") (pintype "passive"))
    )
    (net (code "122") (name "PC2") (class "Default")
      (node (ref "IC1") (pin "10") (pinfunction "PC2_10") (pintype "bidirectional"))
      (node (ref "X27") (pin "2") (pinfunction "2_2") (pintype "passive"))
    )
    (net (code "123") (name "PC4") (class "Default")
      (node (ref "IC1") (pin "24") (pinfunction "PC4_24") (pintype "bidirectional"))
      (node (ref "X28") (pin "2") (pinfunction "2_2") (pintype "passive"))
    )
    (net (code "124") (name "PC8") (class "Default")
      (node (ref "IC1") (pin "39") (pinfunction "PC8_39") (pintype "bidirectional"))
      (node (ref "R63") (pin "1") (pinfunction "1_1") (pintype "passive"))
    )
    (net (code "125") (name "PC9") (class "Default")
      (node (ref "IC1") (pin "40") (pinfunction "PC9_40") (pintype "bidirectional"))
      (node (ref "R61") (pin "1") (pinfunction "1_1") (pintype "passive"))
    )
    (net (code "126") (name "PC13") (class "Default")
      (node (ref "IC1") (pin "2") (pinfunction "PC13_2") (pintype "bidirectional"))
      (node (ref "X34") (pin "2") (pinfunction "2_2") (pintype "passive"))
    )
    (net (code "127") (name "PC14") (class "Default")
      (node (ref "IC1") (pin "3") (pinfunction "PC14-OSC32_IN_3") (pintype "bidirectional"))
      (node (ref "X35") (pin "2") (pinfunction "2_2") (pintype "passive"))
    )
    (net (code "128") (name "PC15") (class "Default")
      (node (ref "C1") (pin "2") (pinfunction "2_2") (pintype "bidirectional"))
      (node (ref "IC1") (pin "4") (pinfunction "PC15-OSC32_OUT_4") (pintype "bidirectional"))
      (node (ref "S1") (pin "A1") (pinfunction "NO_1_A1") (pintype "bidirectional"))
    )
    (net (code "129") (name "PH0") (class "Default")
      (node (ref "IC1") (pin "5") (pinfunction "PH0-OSC_IN_5") (pintype "bidirectional"))
      (node (ref "X32") (pin "2") (pinfunction "2_2") (pintype "passive"))
    )
    (net (code "130") (name "PH1") (class "Default")
      (node (ref "IC1") (pin "6") (pinfunction "PH1-OSC_OUT_6") (pintype "bidirectional"))
      (node (ref "X33") (pin "2") (pinfunction "2_2") (pintype "passive"))
    )
    (net (code "131") (name "SCK_5V") (class "Default")
      (node (ref "IC4") (pin "13") (pinfunction "CLK_13") (pintype "bidirectional"))
      (node (ref "Q5") (pin "3") (pinfunction "D_3") (pintype "bidirectional"))
      (node (ref "R30") (pin "2") (pinfunction "2_2") (pintype "passive"))
    )
    (net (code "132") (name "SCL1") (class "Default")
      (node (ref "IC1") (pin "61") (pinfunction "PB8_61") (pintype "bidirectional"))
      (node (ref "X14") (pin "3") (pinfunction "3_3") (pintype "passive"))
    )
    (net (code "133") (name "SCL2") (class "Default")
      (node (ref "IC1") (pin "28") (pinfunction "PB10_28") (pintype "bidirectional"))
      (node (ref "X17") (pin "3") (pinfunction "3_3") (pintype "passive"))
    )
    (net (code "134") (name "SDA1") (class "Default")
      (node (ref "IC1") (pin "62") (pinfunction "PB9_62") (pintype "bidirectional"))
      (node (ref "X14") (pin "2") (pinfunction "2_2") (pintype "passive"))
    )
    (net (code "135") (name "SDA2") (class "Default")
      (node (ref "IC1") (pin "29") (pinfunction "PB11_29") (pintype "bidirectional"))
      (node (ref "X17") (pin "2") (pinfunction "2_2") (pintype "passive"))
    )
    (net (code "136") (name "SPI1_MISO") (class "Default")
      (node (ref "IC1") (pin "22") (pinfunction "PA6_22") (pintype "bidirectional"))
      (node (ref "Q3") (pin "2") (pinfunction "S_2") (pintype "bidirectional"))
      (node (ref "R27") (pin "2") (pinfunction "2_2") (pintype "passive"))
    )
    (net (code "137") (name "SPI1_MOSI") (class "Default")
      (node (ref "IC1") (pin "23") (pinfunction "PA7_23") (pintype "bidirectional"))
      (node (ref "Q2") (pin "2") (pinfunction "S_2") (pintype "bidirectional"))
      (node (ref "R25") (pin "2") (pinfunction "2_2") (pintype "passive"))
    )
    (net (code "138") (name "SPI1_NSS") (class "Default")
      (node (ref "IC1") (pin "20") (pinfunction "PA4_20") (pintype "bidirectional"))
      (node (ref "Q1") (pin "2") (pinfunction "S_2") (pintype "bidirectional"))
      (node (ref "R23") (pin "2") (pinfunction "2_2") (pintype "passive"))
    )
    (net (code "139") (name "SPI1_SCK") (class "Default")
      (node (ref "IC1") (pin "21") (pinfunction "PA5_21") (pintype "bidirectional"))
      (node (ref "Q5") (pin "2") (pinfunction "S_2") (pintype "bidirectional"))
      (node (ref "R29") (pin "2") (pinfunction "2_2") (pintype "passive"))
    )
    (net (code "140") (name "SPI2_MISO") (class "Default")
      (node (ref "IC1") (pin "35") (pinfunction "PB14_35") (pintype "bidirectional"))
      (node (ref "X8") (pin "2") (pinfunction "2_2") (pintype "passive"))
    )
    (net (code "141") (name "SPI2_MOSI") (class "Default")
      (node (ref "IC1") (pin "36") (pinfunction "PB15_36") (pintype "bidirectional"))
      (node (ref "X8") (pin "1") (pinfunction "1_1") (pintype "passive"))
    )
    (net (code "142") (name "SPI2_NSS") (class "Default")
      (node (ref "IC1") (pin "33") (pinfunction "PB12_33") (pintype "bidirectional"))
      (node (ref "X8") (pin "4") (pinfunction "4_4") (pintype "passive"))
    )
    (net (code "143") (name "SPI2_SCK") (class "Default")
      (node (ref "IC1") (pin "34") (pinfunction "PB13_34") (pintype "bidirectional"))
      (node (ref "X8") (pin "3") (pinfunction "3_3") (pintype "passive"))
    )
    (net (code "144") (name "SWCLK") (class "Default")
      (node (ref "IC1") (pin "49") (pinfunction "PA14_49") (pintype "bidirectional"))
      (node (ref "SL1") (pin "2") (pinfunction "2_2") (pintype "passive"))
    )
    (net (code "145") (name "SWDIO") (class "Default")
      (node (ref "IC1") (pin "46") (pinfunction "PA13_46") (pintype "bidirectional"))
      (node (ref "SL1") (pin "4") (pinfunction "4_4") (pintype "passive"))
    )
    (net (code "146") (name "SWO") (class "Default")
      (node (ref "SL1") (pin "6") (pinfunction "6_6") (pintype "passive"))
    )
    (net (code "147") (name "UART_RX") (class "Default")
      (node (ref "IC1") (pin "54") (pinfunction "PD2_54") (pintype "bidirectional"))
      (node (ref "X11") (pin "3") (pinfunction "3_3") (pintype "passive"))
    )
    (net (code "148") (name "UART_TX") (class "Default")
      (node (ref "IC1") (pin "53") (pinfunction "PC12_53") (pintype "bidirectional"))
      (node (ref "X11") (pin "2") (pinfunction "2_2") (pintype "passive"))
    )
    (net (code "149") (name "USART1_RX") (class "Default")
      (node (ref "IC1") (pin "17") (pinfunction "PA3_17") (pintype "bidirectional"))
      (node (ref "R57") (pin "1") (pinfunction "1_1") (pintype "passive"))
      (node (ref "X9") (pin "3") (pinfunction "3_3") (pintype "passive"))
    )
    (net (code "150") (name "USART1_TX") (class "Default")
      (node (ref "IC1") (pin "16") (pinfunction "PA2_16") (pintype "bidirectional"))
      (node (ref "R55") (pin "1") (pinfunction "1_1") (pintype "passive"))
      (node (ref "X9") (pin "2") (pinfunction "2_2") (pintype "passive"))
    )
    (net (code "151") (name "USART2_RX") (class "Default")
      (node (ref "IC1") (pin "52") (pinfunction "PC11_52") (pintype "bidirectional"))
      (node (ref "X13") (pin "3") (pinfunction "3_3") (pintype "passive"))
    )
    (net (code "152") (name "USART2_TX") (class "Default")
      (node (ref "IC1") (pin "51") (pinfunction "PC10_51") (pintype "bidirectional"))
      (node (ref "X13") (pin "2") (pinfunction "2_2") (pintype "passive"))
    )
    (net (code "153") (name "VCAP") (class "Default")
      (node (ref "C20") (pin "2") (pinfunction "2_2") (pintype "bidirectional"))
      (node (ref "C21") (pin "2") (pinfunction "2_2") (pintype "bidirectional"))
      (node (ref "IC1") (pin "30") (pinfunction "VCAP_1_30") (pintype "power_in"))
    )
    (net (code "154") (name "unconnected-(IC1-PC0-Pad8)") (class "Default")
      (node (ref "IC1") (pin "8") (pinfunction "PC0_8") (pintype "bidirectional"))
    )
    (net (code "155") (name "unconnected-(IC1-PC3-Pad11)") (class "Default")
      (node (ref "IC1") (pin "11") (pinfunction "PC3_11") (pintype "bidirectional"))
    )
    (net (code "156") (name "unconnected-(J1-PadMH1)") (class "Default")
      (node (ref "J1") (pin "MH1") (pinfunction "MH1_MH1") (pintype "bidirectional"))
    )
    (net (code "157") (name "unconnected-(J1-PadMH2)") (class "Default")
      (node (ref "J1") (pin "MH2") (pinfunction "MH2_MH2") (pintype "bidirectional"))
    )
    (net (code "158") (name "unconnected-(J1-PadMH3)") (class "Default")
      (node (ref "J1") (pin "MH3") (pinfunction "MH3_MH3") (pintype "bidirectional"))
    )
    (net (code "159") (name "unconnected-(J1-PadMH4)") (class "Default")
      (node (ref "J1") (pin "MH4") (pinfunction "MH4_MH4") (pintype "bidirectional"))
    )
    (net (code "160") (name "unconnected-(J2-PadMH1)") (class "Default")
      (node (ref "J2") (pin "MH1") (pinfunction "MH1_MH1") (pintype "bidirectional"))
    )
    (net (code "161") (name "unconnected-(J2-PadMH2)") (class "Default")
      (node (ref "J2") (pin "MH2") (pinfunction "MH2_MH2") (pintype "bidirectional"))
    )
    (net (code "162") (name "unconnected-(J2-PadMH3)") (class "Default")
      (node (ref "J2") (pin "MH3") (pinfunction "MH3_MH3") (pintype "bidirectional"))
    )
    (net (code "163") (name "unconnected-(J2-PadMH4)") (class "Default")
      (node (ref "J2") (pin "MH4") (pinfunction "MH4_MH4") (pintype "bidirectional"))
    )
    (net (code "164") (name "unconnected-(S1-COM_2-PadD1)") (class "Default")
      (node (ref "S1") (pin "D1") (pinfunction "COM_2_D1") (pintype "bidirectional"))
    )
    (net (code "165") (name "unconnected-(S1-NO_2-PadB1)") (class "Default")
      (node (ref "S1") (pin "B1") (pinfunction "NO_2_B1") (pintype "bidirectional"))
    )
    (net (code "166") (name "unconnected-(S2-NO_2-PadB1)") (class "Default")
      (node (ref "S2") (pin "B1") (pinfunction "NO_2_B1") (pintype "bidirectional"))
    )
    (net (code "167") (name "unconnected-(X1-Pad2)") (class "Default")
      (node (ref "X1") (pin "2") (pinfunction "2_2") (pintype "passive"))
    )
    (net (code "168") (name "unconnected-(X2-Pad2)") (class "Default")
      (node (ref "X2") (pin "2") (pinfunction "2_2") (pintype "passive"))
    )
    (net (code "169") (name "unconnected-(X3-Pad2)") (class "Default")
      (node (ref "X3") (pin "2") (pinfunction "2_2") (pintype "passive"))
    )
    (net (code "170") (name "unconnected-(X4-Pad2)") (class "Default")
      (node (ref "X4") (pin "2") (pinfunction "2_2") (pintype "passive"))
    )
    (net (code "171") (name "unconnected-(X5-Pad2)") (class "Default")
      (node (ref "X5") (pin "2") (pinfunction "2_2") (pintype "passive"))
    )
    (net (code "172") (name "unconnected-(X6-Pad2)") (class "Default")
      (node (ref "X6") (pin "2") (pinfunction "2_2") (pintype "passive"))
    )
  )
)
